# tc_board.net
KiCad netlist of a schematic drawn in EAGLE
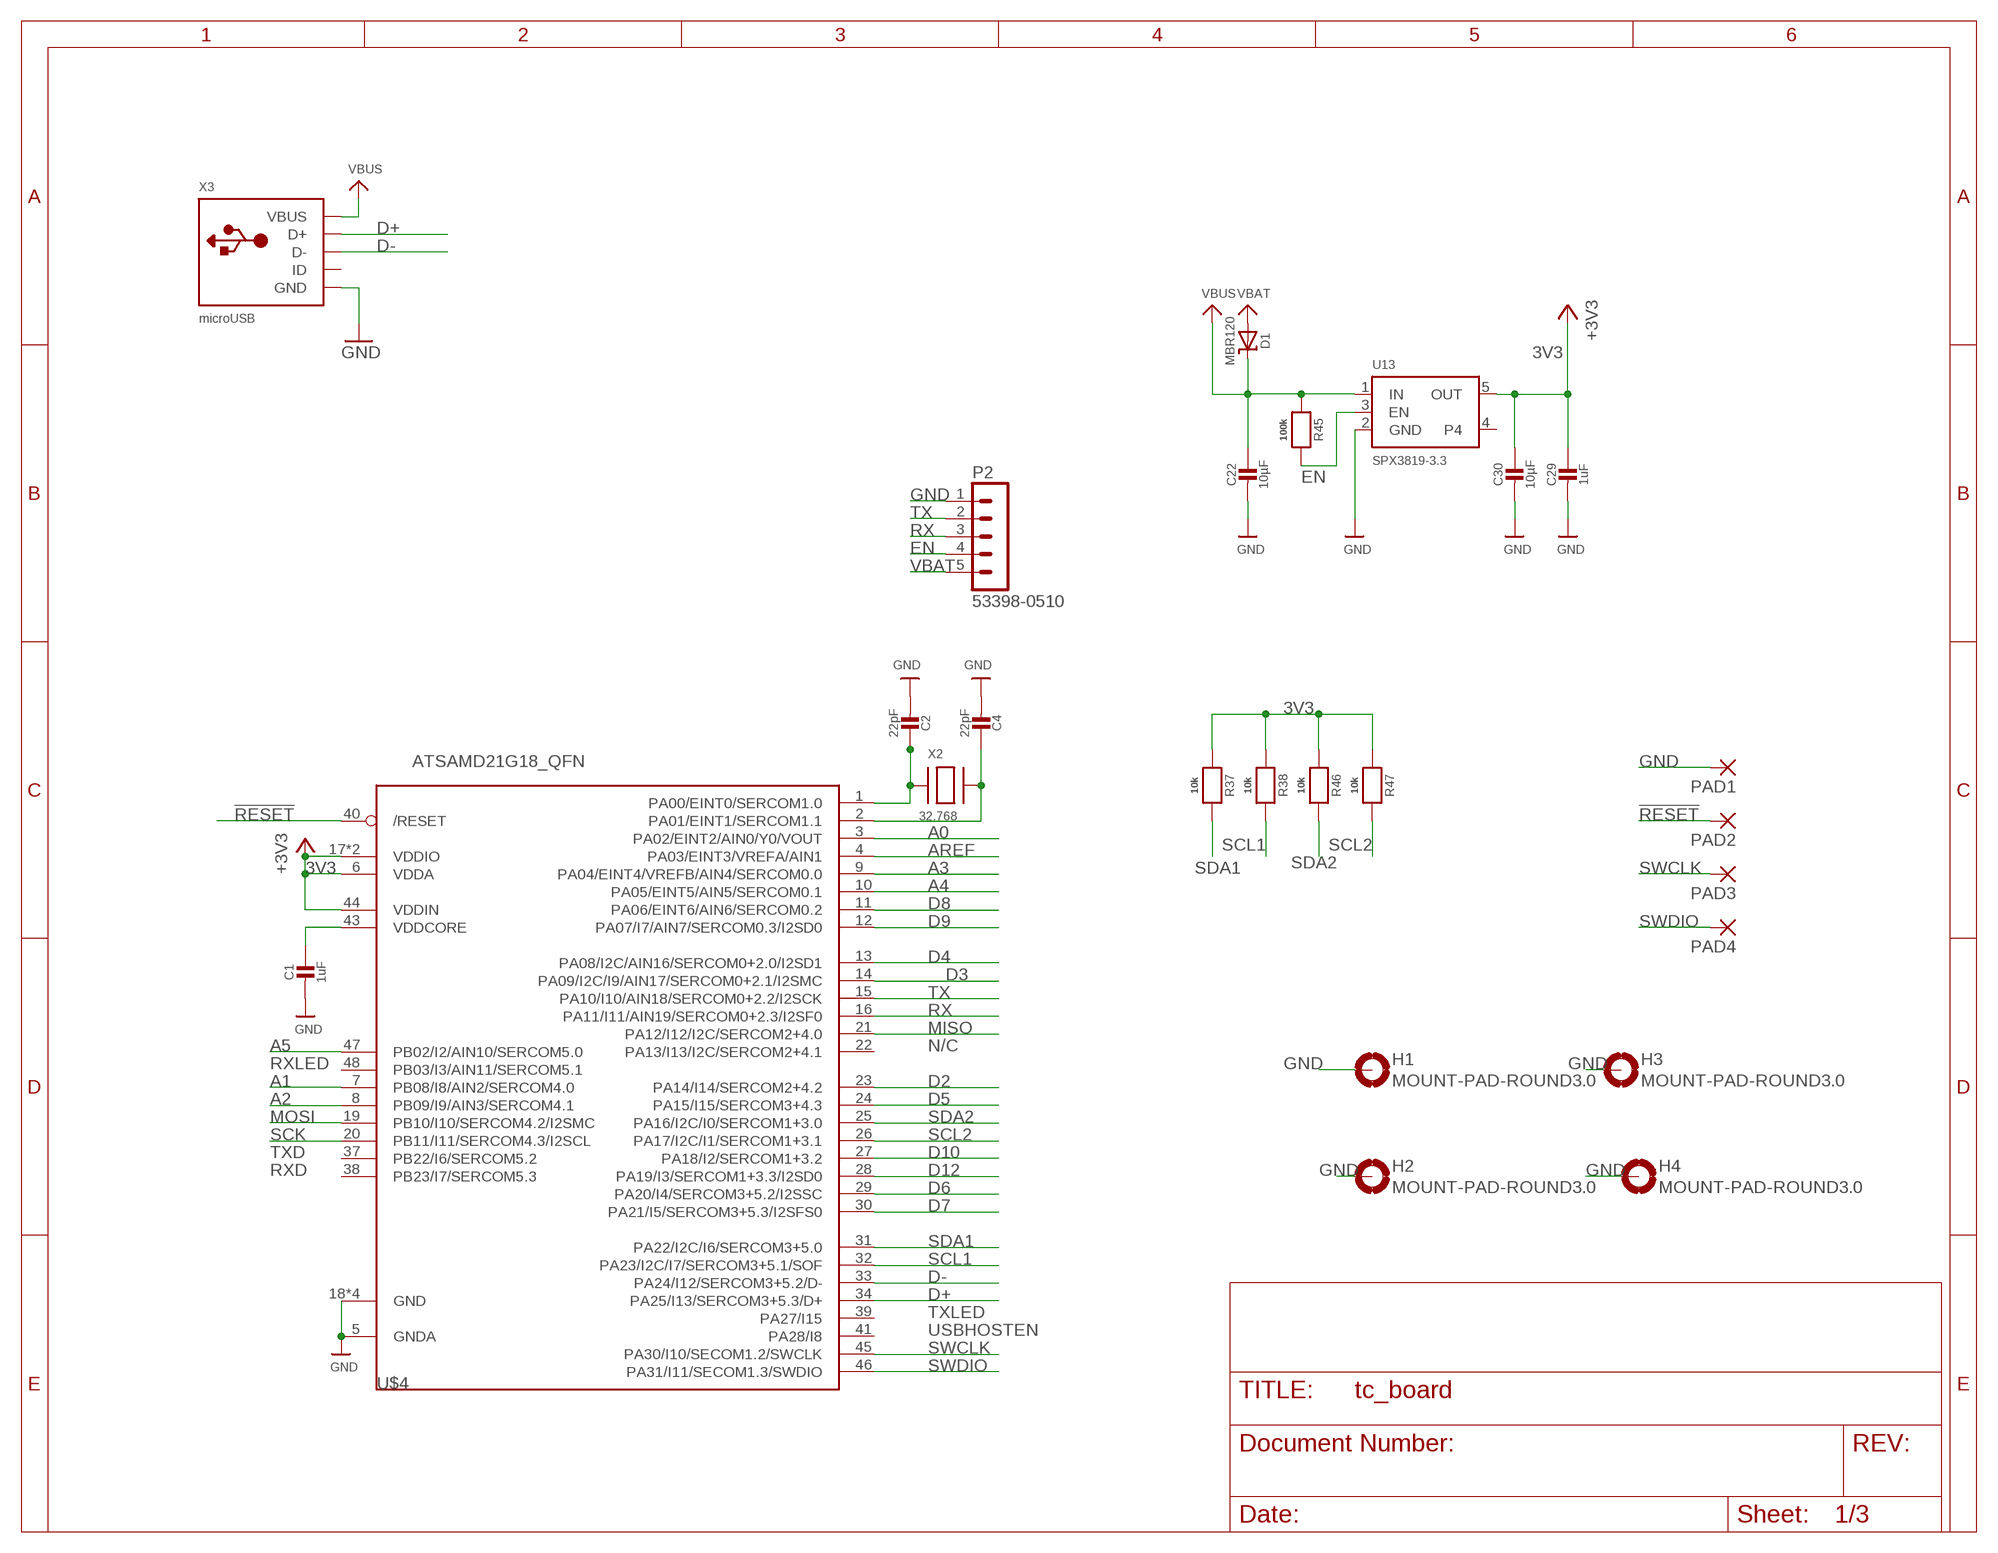
[diagram p0: schematic, sheet 1]
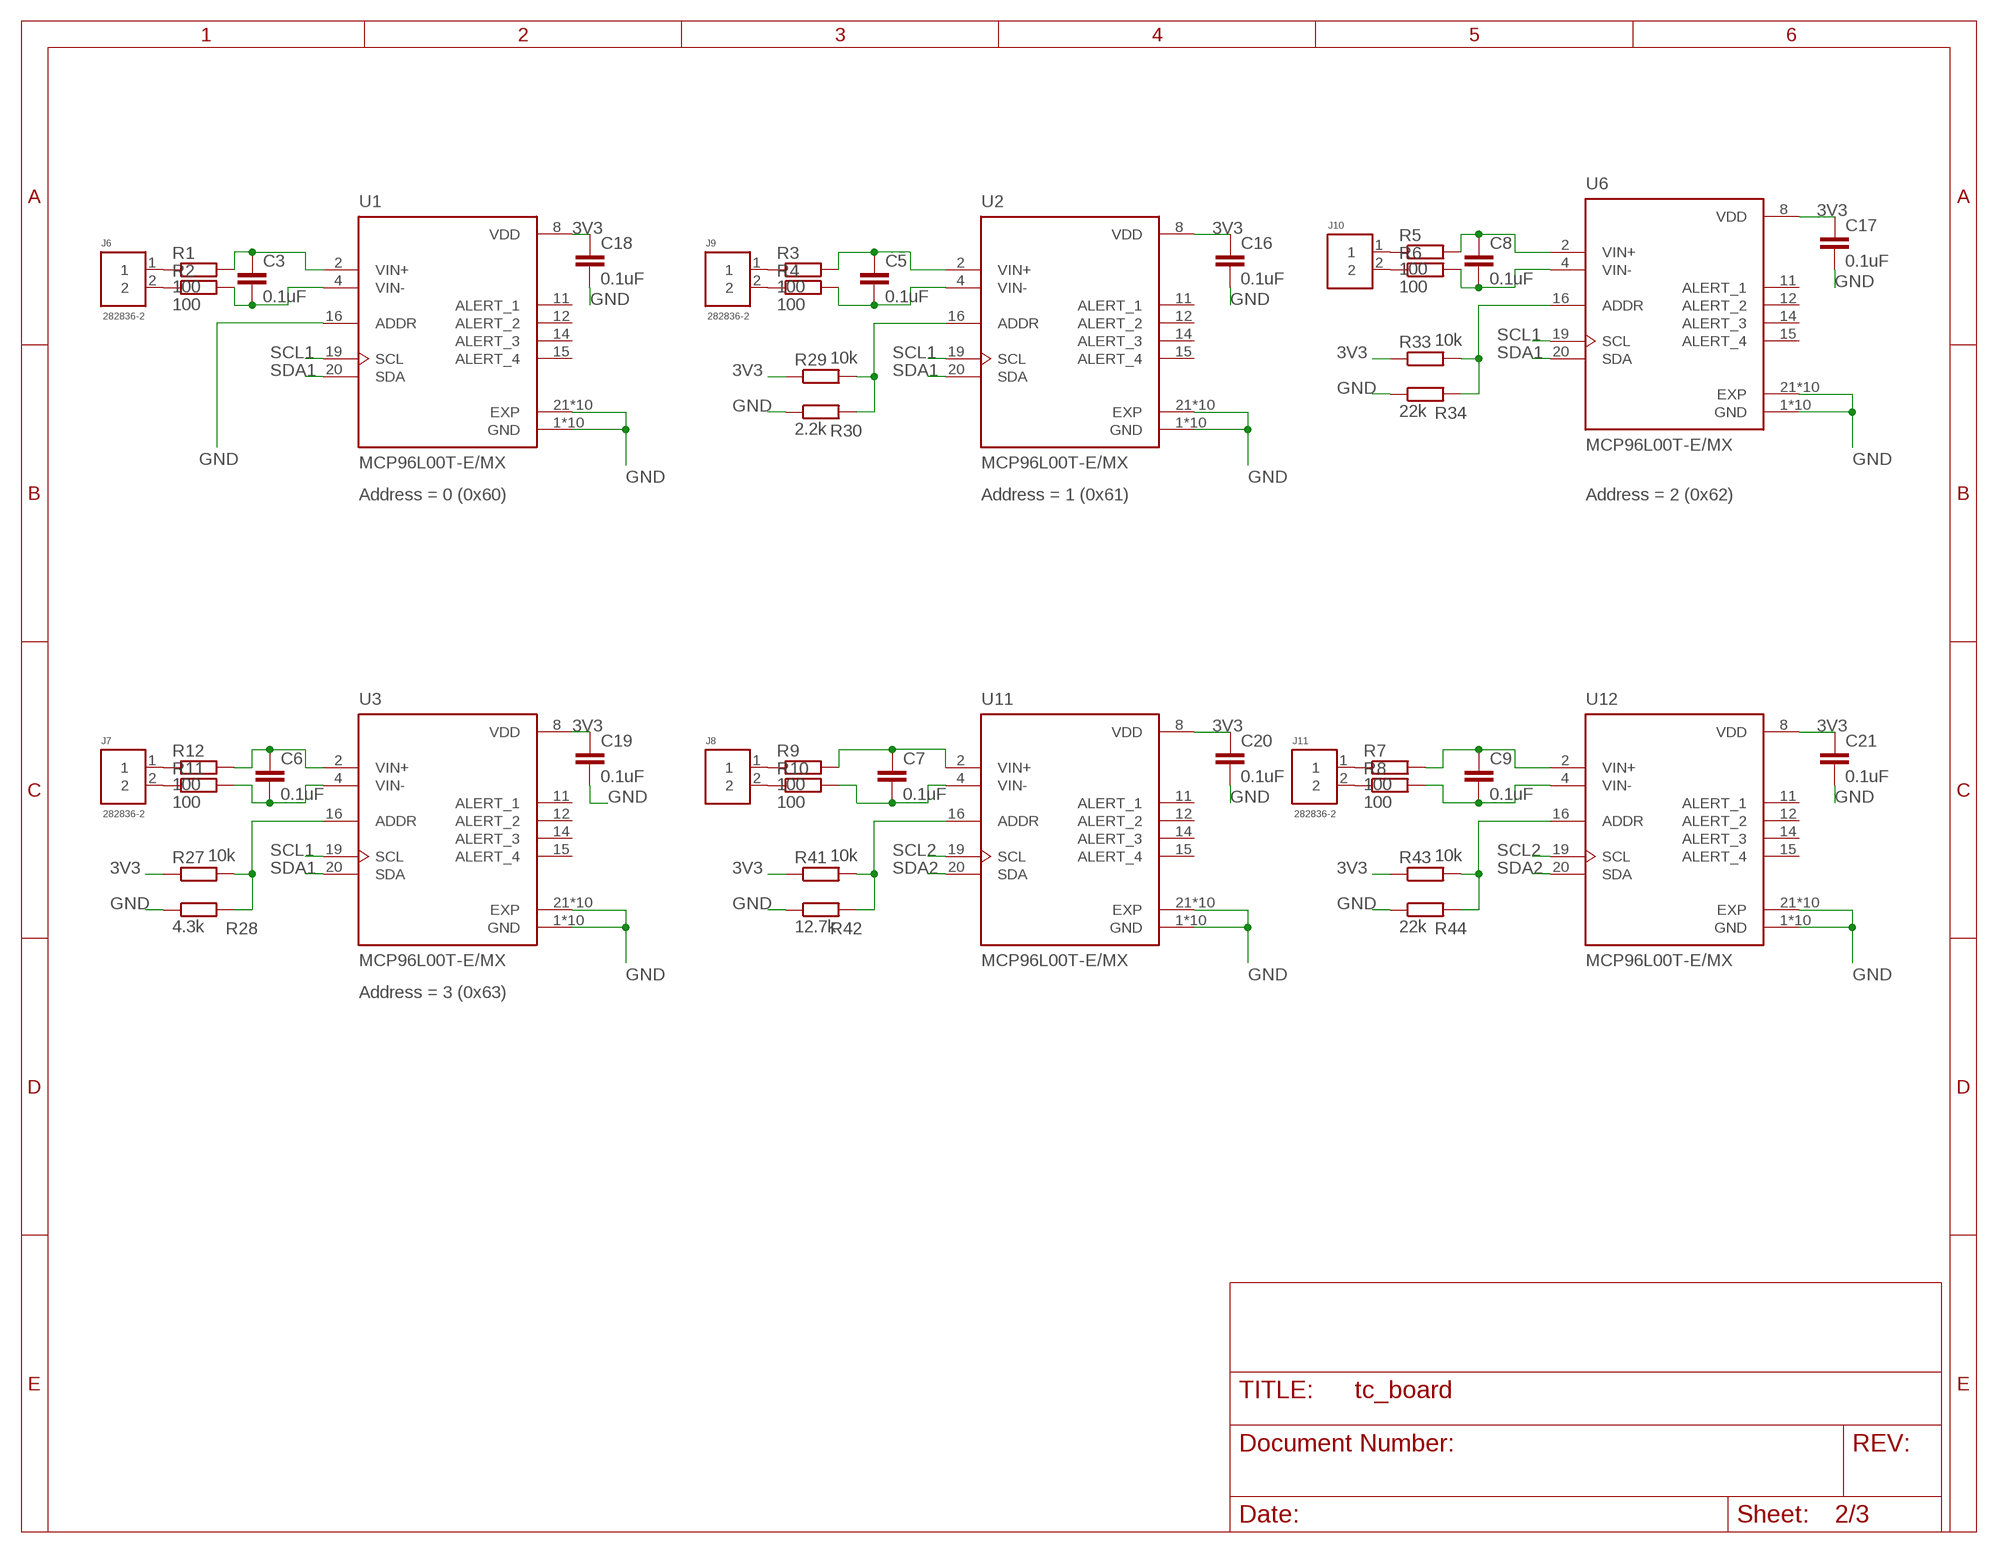
[diagram p1: schematic, sheet 2]
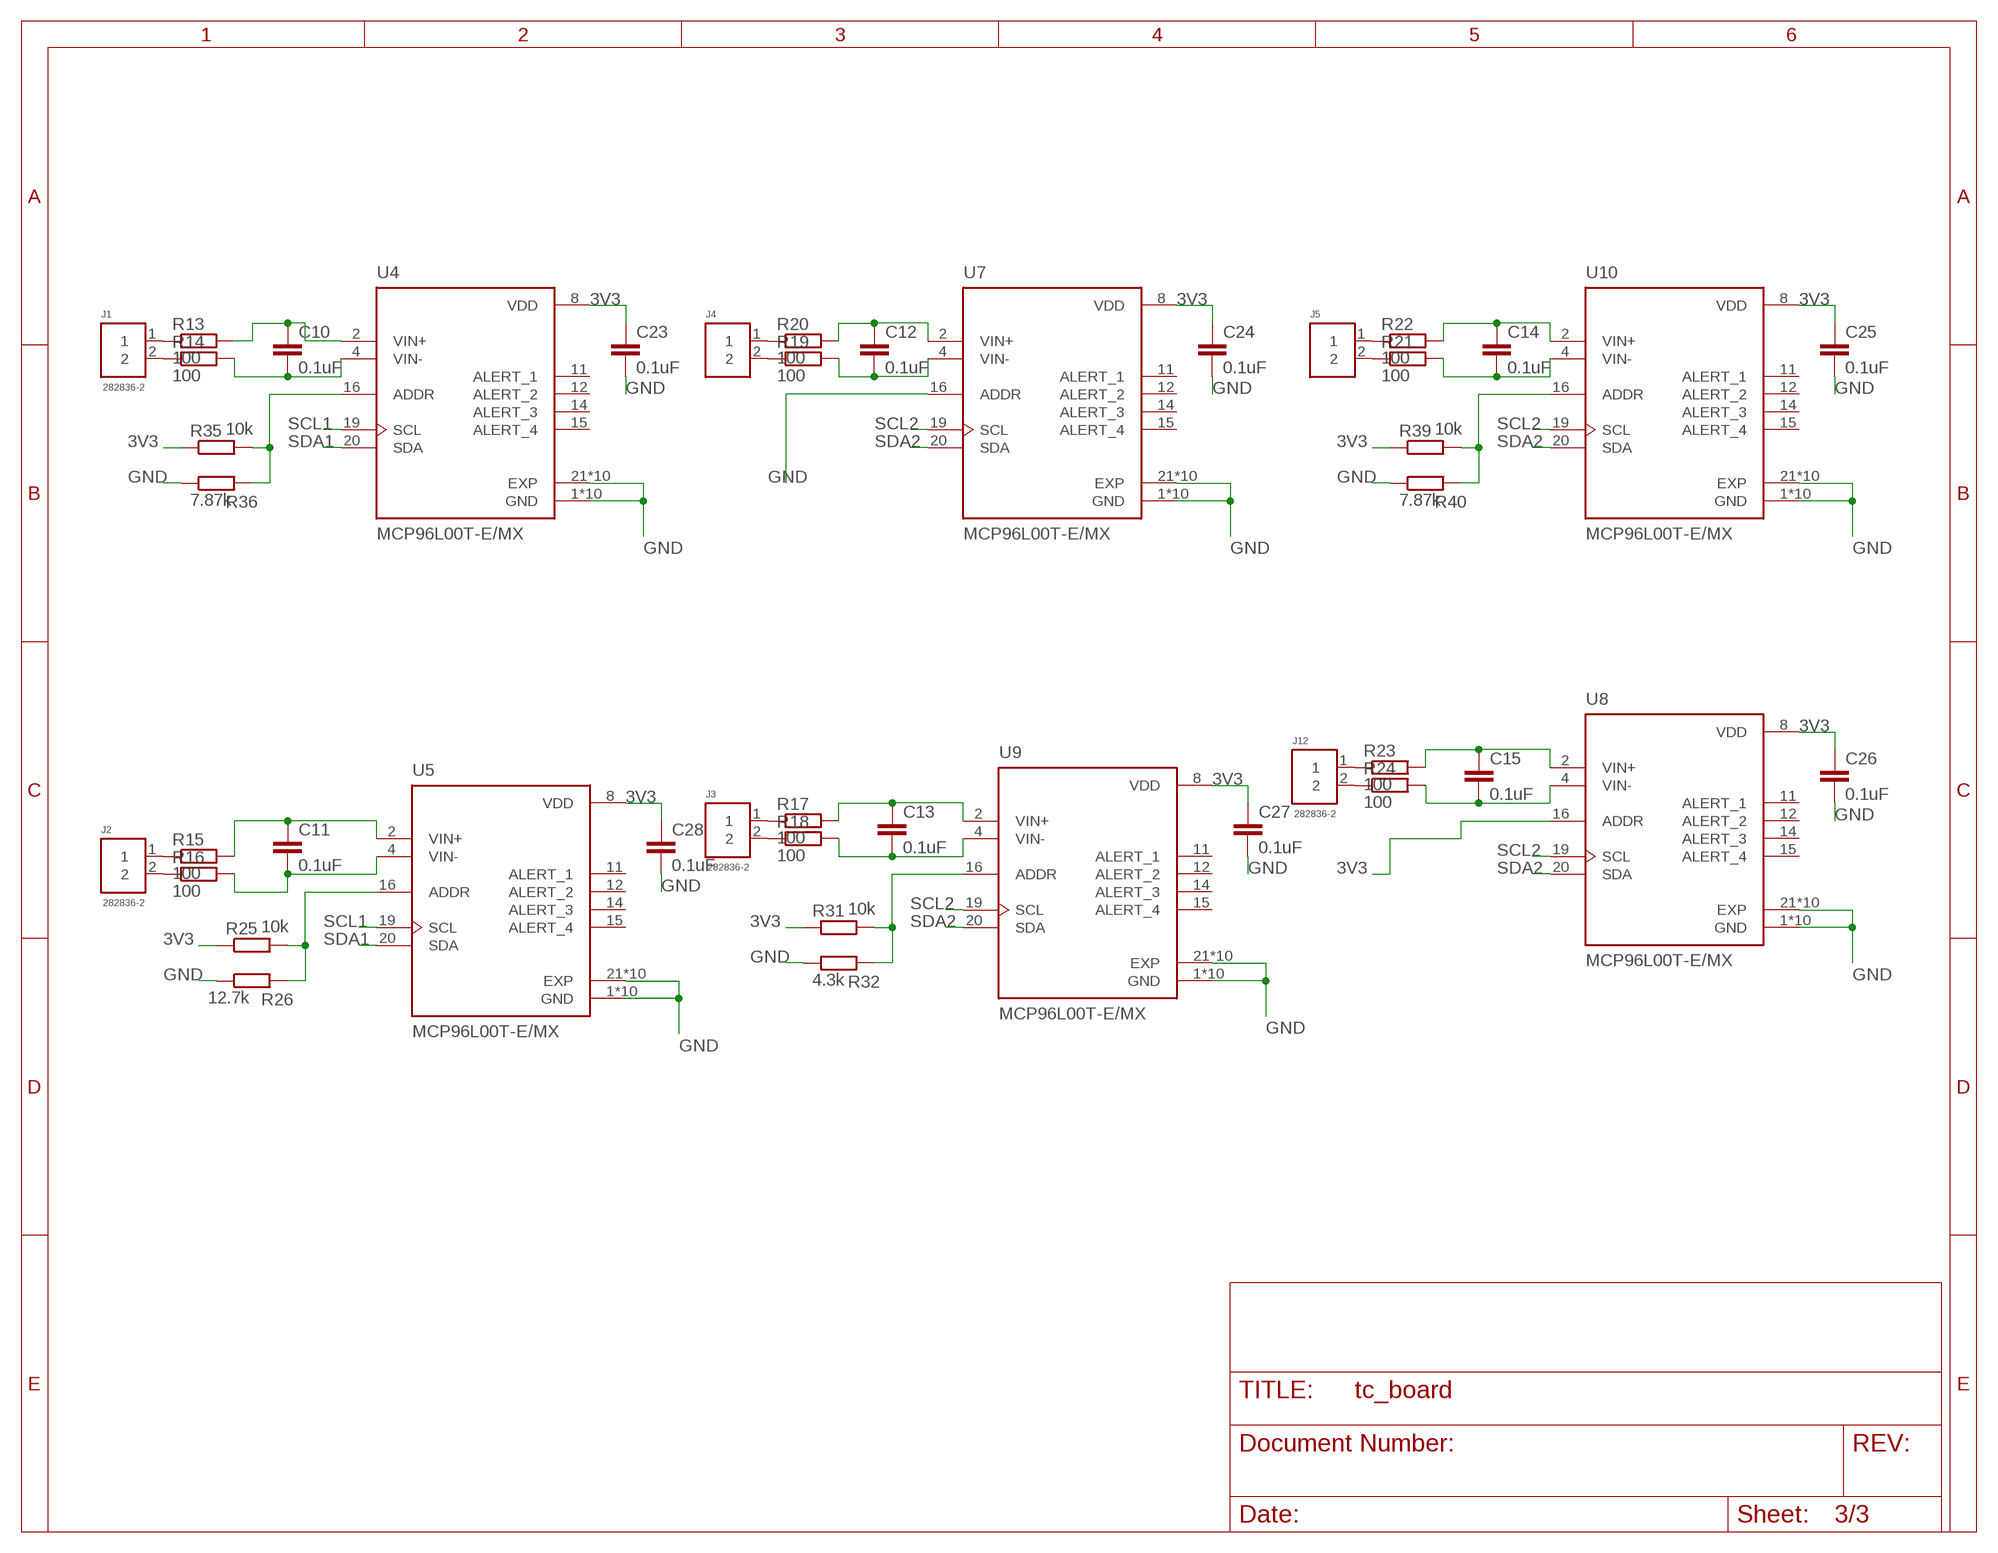
[diagram p2: schematic, sheet 3]

(export (version "E")
  (design (tool "Eeschema 10.0.6"))
  (components
    (comp (ref "C3")
      (value "0.1uF")
      (footprint "eagle-import:C0603")
      (libsource (lib "eagle-import") (part "C-EUC0603"))
    )
    (comp (ref "C5")
      (value "0.1uF")
      (footprint "eagle-import:C0603")
      (libsource (lib "eagle-import") (part "C-EUC0603"))
    )
    (comp (ref "C6")
      (value "0.1uF")
      (footprint "eagle-import:C0603")
      (libsource (lib "eagle-import") (part "C-EUC0603"))
    )
    (comp (ref "C7")
      (value "0.1uF")
      (footprint "eagle-import:C0603")
      (libsource (lib "eagle-import") (part "C-EUC0603"))
    )
    (comp (ref "C8")
      (value "0.1uF")
      (footprint "eagle-import:C0603")
      (libsource (lib "eagle-import") (part "C-EUC0603"))
    )
    (comp (ref "C9")
      (value "0.1uF")
      (footprint "eagle-import:C0603")
      (libsource (lib "eagle-import") (part "C-EUC0603"))
    )
    (comp (ref "C16")
      (value "0.1uF")
      (footprint "eagle-import:C0603")
      (libsource (lib "eagle-import") (part "C-EUC0603"))
    )
    (comp (ref "C17")
      (value "0.1uF")
      (footprint "eagle-import:C0603")
      (libsource (lib "eagle-import") (part "C-EUC0603"))
    )
    (comp (ref "C18")
      (value "0.1uF")
      (footprint "eagle-import:C0603")
      (libsource (lib "eagle-import") (part "C-EUC0603"))
    )
    (comp (ref "C19")
      (value "0.1uF")
      (footprint "eagle-import:C0603")
      (libsource (lib "eagle-import") (part "C-EUC0603"))
    )
    (comp (ref "C20")
      (value "0.1uF")
      (footprint "eagle-import:C0603")
      (libsource (lib "eagle-import") (part "C-EUC0603"))
    )
    (comp (ref "C21")
      (value "0.1uF")
      (footprint "eagle-import:C0603")
      (libsource (lib "eagle-import") (part "C-EUC0603"))
    )
    (comp (ref "J6")
      (value "282836-2")
      (footprint "eagle-import:CONN_282836-2")
      (fields (field (name "MF") "TE Connectivity") (field (name "MP") "2828362"))
      (libsource (lib "eagle-import") (part "282836-2"))
    )
    (comp (ref "J7")
      (value "282836-2")
      (footprint "eagle-import:CONN_282836-2")
      (fields (field (name "MF") "TE Connectivity") (field (name "MP") "2828362"))
      (libsource (lib "eagle-import") (part "282836-2"))
    )
    (comp (ref "J8")
      (value "282836-2")
      (footprint "eagle-import:CONN_282836-2")
      (fields (field (name "MF") "TE Connectivity") (field (name "MP") "2828362"))
      (libsource (lib "eagle-import") (part "282836-2"))
    )
    (comp (ref "J9")
      (value "282836-2")
      (footprint "eagle-import:CONN_282836-2")
      (fields (field (name "MF") "TE Connectivity") (field (name "MP") "2828362"))
      (libsource (lib "eagle-import") (part "282836-2"))
    )
    (comp (ref "J10")
      (value "282836-2")
      (footprint "eagle-import:CONN_282836-2")
      (fields (field (name "MF") "TE Connectivity") (field (name "MP") "2828362"))
      (libsource (lib "eagle-import") (part "282836-2"))
    )
    (comp (ref "J11")
      (value "282836-2")
      (footprint "eagle-import:CONN_282836-2")
      (fields (field (name "MF") "TE Connectivity") (field (name "MP") "2828362"))
      (libsource (lib "eagle-import") (part "282836-2"))
    )
    (comp (ref "R1")
      (value "100")
      (footprint "eagle-import:R0603")
      (libsource (lib "eagle-import") (part "R-EU_R0603"))
    )
    (comp (ref "R2")
      (value "100")
      (footprint "eagle-import:R0603")
      (libsource (lib "eagle-import") (part "R-EU_R0603"))
    )
    (comp (ref "R3")
      (value "100")
      (footprint "eagle-import:R0603")
      (libsource (lib "eagle-import") (part "R-EU_R0603"))
    )
    (comp (ref "R4")
      (value "100")
      (footprint "eagle-import:R0603")
      (libsource (lib "eagle-import") (part "R-EU_R0603"))
    )
    (comp (ref "R5")
      (value "100")
      (footprint "eagle-import:R0603")
      (libsource (lib "eagle-import") (part "R-EU_R0603"))
    )
    (comp (ref "R6")
      (value "100")
      (footprint "eagle-import:R0603")
      (libsource (lib "eagle-import") (part "R-EU_R0603"))
    )
    (comp (ref "R7")
      (value "100")
      (footprint "eagle-import:R0603")
      (libsource (lib "eagle-import") (part "R-EU_R0603"))
    )
    (comp (ref "R8")
      (value "100")
      (footprint "eagle-import:R0603")
      (libsource (lib "eagle-import") (part "R-EU_R0603"))
    )
    (comp (ref "R9")
      (value "100")
      (footprint "eagle-import:R0603")
      (libsource (lib "eagle-import") (part "R-EU_R0603"))
    )
    (comp (ref "R10")
      (value "100")
      (footprint "eagle-import:R0603")
      (libsource (lib "eagle-import") (part "R-EU_R0603"))
    )
    (comp (ref "R11")
      (value "100")
      (footprint "eagle-import:R0603")
      (libsource (lib "eagle-import") (part "R-EU_R0603"))
    )
    (comp (ref "R12")
      (value "100")
      (footprint "eagle-import:R0603")
      (libsource (lib "eagle-import") (part "R-EU_R0603"))
    )
    (comp (ref "R27")
      (value "10k")
      (footprint "eagle-import:R0603")
      (libsource (lib "eagle-import") (part "R-EU_R0603"))
    )
    (comp (ref "R28")
      (value "4.3k")
      (footprint "eagle-import:R0603")
      (libsource (lib "eagle-import") (part "R-EU_R0603"))
    )
    (comp (ref "R29")
      (value "10k")
      (footprint "eagle-import:R0603")
      (libsource (lib "eagle-import") (part "R-EU_R0603"))
    )
    (comp (ref "R30")
      (value "2.2k")
      (footprint "eagle-import:R0603")
      (libsource (lib "eagle-import") (part "R-EU_R0603"))
    )
    (comp (ref "R33")
      (value "10k")
      (footprint "eagle-import:R0603")
      (libsource (lib "eagle-import") (part "R-EU_R0603"))
    )
    (comp (ref "R34")
      (value "22k")
      (footprint "eagle-import:R0603")
      (libsource (lib "eagle-import") (part "R-EU_R0603"))
    )
    (comp (ref "R41")
      (value "10k")
      (footprint "eagle-import:R0603")
      (libsource (lib "eagle-import") (part "R-EU_R0603"))
    )
    (comp (ref "R42")
      (value "12.7k")
      (footprint "eagle-import:R0603")
      (libsource (lib "eagle-import") (part "R-EU_R0603"))
    )
    (comp (ref "R43")
      (value "10k")
      (footprint "eagle-import:R0603")
      (libsource (lib "eagle-import") (part "R-EU_R0603"))
    )
    (comp (ref "R44")
      (value "22k")
      (footprint "eagle-import:R0603")
      (libsource (lib "eagle-import") (part "R-EU_R0603"))
    )
    (comp (ref "U1")
      (value "MCP96L00T-E/MX")
      (footprint "eagle-import:QFN65P500X500X100-21N_MCP96L00T-E_MX")
      (fields
        (field (name "DIGI-KEY_PART_NUMBER") "MCP96L00T-E/MXCT-ND")
        (field (name "MF") "Microchip Technology")
      )
      (libsource (lib "eagle-import") (part "MCP96L00T-E/MX"))
    )
    (comp (ref "U2")
      (value "MCP96L00T-E/MX")
      (footprint "eagle-import:QFN65P500X500X100-21N_MCP96L00T-E_MX")
      (fields
        (field (name "DIGI-KEY_PART_NUMBER") "MCP96L00T-E/MXCT-ND")
        (field (name "MF") "Microchip Technology")
      )
      (libsource (lib "eagle-import") (part "MCP96L00T-E/MX"))
    )
    (comp (ref "U3")
      (value "MCP96L00T-E/MX")
      (footprint "eagle-import:QFN65P500X500X100-21N_MCP96L00T-E_MX")
      (fields
        (field (name "DIGI-KEY_PART_NUMBER") "MCP96L00T-E/MXCT-ND")
        (field (name "MF") "Microchip Technology")
      )
      (libsource (lib "eagle-import") (part "MCP96L00T-E/MX"))
    )
    (comp (ref "U6")
      (value "MCP96L00T-E/MX")
      (footprint "eagle-import:QFN65P500X500X100-21N_MCP96L00T-E_MX")
      (fields
        (field (name "DIGI-KEY_PART_NUMBER") "MCP96L00T-E/MXCT-ND")
        (field (name "MF") "Microchip Technology")
      )
      (libsource (lib "eagle-import") (part "MCP96L00T-E/MX"))
    )
    (comp (ref "U11")
      (value "MCP96L00T-E/MX")
      (footprint "eagle-import:QFN65P500X500X100-21N_MCP96L00T-E_MX")
      (fields
        (field (name "DIGI-KEY_PART_NUMBER") "MCP96L00T-E/MXCT-ND")
        (field (name "MF") "Microchip Technology")
      )
      (libsource (lib "eagle-import") (part "MCP96L00T-E/MX"))
    )
    (comp (ref "U12")
      (value "MCP96L00T-E/MX")
      (footprint "eagle-import:QFN65P500X500X100-21N_MCP96L00T-E_MX")
      (fields
        (field (name "DIGI-KEY_PART_NUMBER") "MCP96L00T-E/MXCT-ND")
        (field (name "MF") "Microchip Technology")
      )
      (libsource (lib "eagle-import") (part "MCP96L00T-E/MX"))
    )
    (comp (ref "C1")
      (value "1uF")
      (footprint "eagle-import:0603-NO")
      (libsource (lib "eagle-import") (part "CAP_CERAMIC0603_NO"))
    )
    (comp (ref "C2")
      (value "22pF")
      (footprint "eagle-import:0603-NO")
      (libsource (lib "eagle-import") (part "CAP_CERAMIC0603_NO"))
    )
    (comp (ref "C4")
      (value "22pF")
      (footprint "eagle-import:0603-NO")
      (libsource (lib "eagle-import") (part "CAP_CERAMIC0603_NO"))
    )
    (comp (ref "C22")
      (value "10µF")
      (footprint "eagle-import:0805-NO")
      (libsource (lib "eagle-import") (part "CAP_CERAMIC0805-NOOUTLINE"))
    )
    (comp (ref "C29")
      (value "1uF")
      (footprint "eagle-import:0603-NO")
      (libsource (lib "eagle-import") (part "CAP_CERAMIC0603_NO"))
    )
    (comp (ref "C30")
      (value "10µF")
      (footprint "eagle-import:0805-NO")
      (libsource (lib "eagle-import") (part "CAP_CERAMIC0805-NOOUTLINE"))
    )
    (comp (ref "D1")
      (value "MBR120")
      (footprint "eagle-import:SOD-123")
      (libsource (lib "eagle-import") (part "DIODE-SCHOTTKYSOD-123"))
    )
    (comp (ref "H1")
      (value "MOUNT-PAD-ROUND3.0")
      (footprint "eagle-import:3,0-PAD")
      (libsource (lib "eagle-import") (part "MOUNT-PAD-ROUND3.0"))
    )
    (comp (ref "H2")
      (value "MOUNT-PAD-ROUND3.0")
      (footprint "eagle-import:3,0-PAD")
      (libsource (lib "eagle-import") (part "MOUNT-PAD-ROUND3.0"))
    )
    (comp (ref "H3")
      (value "MOUNT-PAD-ROUND3.0")
      (footprint "eagle-import:3,0-PAD")
      (libsource (lib "eagle-import") (part "MOUNT-PAD-ROUND3.0"))
    )
    (comp (ref "H4")
      (value "MOUNT-PAD-ROUND3.0")
      (footprint "eagle-import:3,0-PAD")
      (libsource (lib "eagle-import") (part "MOUNT-PAD-ROUND3.0"))
    )
    (comp (ref "P2")
      (value "53398-0510")
      (footprint "eagle-import:53398-0510")
      (libsource (lib "eagle-import") (part "53398-0510"))
    )
    (comp (ref "PAD1")
      (value "SMD2")
      (footprint "eagle-import:SMD1,27-2,54")
      (libsource (lib "eagle-import") (part "SMD2"))
    )
    (comp (ref "PAD2")
      (value "SMD2")
      (footprint "eagle-import:SMD1,27-2,54")
      (libsource (lib "eagle-import") (part "SMD2"))
    )
    (comp (ref "PAD3")
      (value "SMD2")
      (footprint "eagle-import:SMD1,27-2,54")
      (libsource (lib "eagle-import") (part "SMD2"))
    )
    (comp (ref "PAD4")
      (value "SMD2")
      (footprint "eagle-import:SMD1,27-2,54")
      (libsource (lib "eagle-import") (part "SMD2"))
    )
    (comp (ref "R37")
      (value "10k")
      (footprint "eagle-import:0603-NO")
      (libsource (lib "eagle-import") (part "RESISTOR_0603_NOOUT"))
    )
    (comp (ref "R38")
      (value "10k")
      (footprint "eagle-import:0603-NO")
      (libsource (lib "eagle-import") (part "RESISTOR_0603_NOOUT"))
    )
    (comp (ref "R45")
      (value "100k")
      (footprint "eagle-import:0603-NO")
      (libsource (lib "eagle-import") (part "RESISTOR_0603_NOOUT"))
    )
    (comp (ref "R46")
      (value "10k")
      (footprint "eagle-import:0603-NO")
      (libsource (lib "eagle-import") (part "RESISTOR_0603_NOOUT"))
    )
    (comp (ref "R47")
      (value "10k")
      (footprint "eagle-import:0603-NO")
      (libsource (lib "eagle-import") (part "RESISTOR_0603_NOOUT"))
    )
    (comp (ref "U$4")
      (value "ATSAMD21G18_QFN")
      (footprint "eagle-import:TQFN48_7MM")
      (libsource (lib "eagle-import") (part "ATSAMD21J_QFN"))
    )
    (comp (ref "U13")
      (value "SPX3819-3.3")
      (footprint "eagle-import:SOT23-5")
      (libsource (lib "eagle-import") (part "VREG_SOT23-5"))
    )
    (comp (ref "X2")
      (value "32.768")
      (footprint "eagle-import:XTAL3215")
      (libsource (lib "eagle-import") (part "XTAL-3.2X1.5"))
    )
    (comp (ref "X3")
      (value "microUSB")
      (footprint "eagle-import:4UCONN_20329_V2")
      (libsource (lib "eagle-import") (part "USB_MICRO_20329_V2"))
    )
    (comp (ref "C10")
      (value "0.1uF")
      (footprint "eagle-import:C0603")
      (libsource (lib "eagle-import") (part "C-EUC0603"))
    )
    (comp (ref "C11")
      (value "0.1uF")
      (footprint "eagle-import:C0603")
      (libsource (lib "eagle-import") (part "C-EUC0603"))
    )
    (comp (ref "C12")
      (value "0.1uF")
      (footprint "eagle-import:C0603")
      (libsource (lib "eagle-import") (part "C-EUC0603"))
    )
    (comp (ref "C13")
      (value "0.1uF")
      (footprint "eagle-import:C0603")
      (libsource (lib "eagle-import") (part "C-EUC0603"))
    )
    (comp (ref "C14")
      (value "0.1uF")
      (footprint "eagle-import:C0603")
      (libsource (lib "eagle-import") (part "C-EUC0603"))
    )
    (comp (ref "C15")
      (value "0.1uF")
      (footprint "eagle-import:C0603")
      (libsource (lib "eagle-import") (part "C-EUC0603"))
    )
    (comp (ref "C23")
      (value "0.1uF")
      (footprint "eagle-import:C0603")
      (libsource (lib "eagle-import") (part "C-EUC0603"))
    )
    (comp (ref "C24")
      (value "0.1uF")
      (footprint "eagle-import:C0603")
      (libsource (lib "eagle-import") (part "C-EUC0603"))
    )
    (comp (ref "C25")
      (value "0.1uF")
      (footprint "eagle-import:C0603")
      (libsource (lib "eagle-import") (part "C-EUC0603"))
    )
    (comp (ref "C26")
      (value "0.1uF")
      (footprint "eagle-import:C0603")
      (libsource (lib "eagle-import") (part "C-EUC0603"))
    )
    (comp (ref "C27")
      (value "0.1uF")
      (footprint "eagle-import:C0603")
      (libsource (lib "eagle-import") (part "C-EUC0603"))
    )
    (comp (ref "C28")
      (value "0.1uF")
      (footprint "eagle-import:C0603")
      (libsource (lib "eagle-import") (part "C-EUC0603"))
    )
    (comp (ref "J1")
      (value "282836-2")
      (footprint "eagle-import:CONN_282836-2")
      (fields (field (name "MF") "TE Connectivity") (field (name "MP") "2828362"))
      (libsource (lib "eagle-import") (part "282836-2"))
    )
    (comp (ref "J2")
      (value "282836-2")
      (footprint "eagle-import:CONN_282836-2")
      (fields (field (name "MF") "TE Connectivity") (field (name "MP") "2828362"))
      (libsource (lib "eagle-import") (part "282836-2"))
    )
    (comp (ref "J3")
      (value "282836-2")
      (footprint "eagle-import:CONN_282836-2")
      (fields (field (name "MF") "TE Connectivity") (field (name "MP") "2828362"))
      (libsource (lib "eagle-import") (part "282836-2"))
    )
    (comp (ref "J4")
      (value "282836-2")
      (footprint "eagle-import:CONN_282836-2")
      (fields (field (name "MF") "TE Connectivity") (field (name "MP") "2828362"))
      (libsource (lib "eagle-import") (part "282836-2"))
    )
    (comp (ref "J5")
      (value "282836-2")
      (footprint "eagle-import:CONN_282836-2")
      (fields (field (name "MF") "TE Connectivity") (field (name "MP") "2828362"))
      (libsource (lib "eagle-import") (part "282836-2"))
    )
    (comp (ref "J12")
      (value "282836-2")
      (footprint "eagle-import:CONN_282836-2")
      (fields (field (name "MF") "TE Connectivity") (field (name "MP") "2828362"))
      (libsource (lib "eagle-import") (part "282836-2"))
    )
    (comp (ref "R13")
      (value "100")
      (footprint "eagle-import:R0603")
      (libsource (lib "eagle-import") (part "R-EU_R0603"))
    )
    (comp (ref "R14")
      (value "100")
      (footprint "eagle-import:R0603")
      (libsource (lib "eagle-import") (part "R-EU_R0603"))
    )
    (comp (ref "R15")
      (value "100")
      (footprint "eagle-import:R0603")
      (libsource (lib "eagle-import") (part "R-EU_R0603"))
    )
    (comp (ref "R16")
      (value "100")
      (footprint "eagle-import:R0603")
      (libsource (lib "eagle-import") (part "R-EU_R0603"))
    )
    (comp (ref "R17")
      (value "100")
      (footprint "eagle-import:R0603")
      (libsource (lib "eagle-import") (part "R-EU_R0603"))
    )
    (comp (ref "R18")
      (value "100")
      (footprint "eagle-import:R0603")
      (libsource (lib "eagle-import") (part "R-EU_R0603"))
    )
    (comp (ref "R19")
      (value "100")
      (footprint "eagle-import:R0603")
      (libsource (lib "eagle-import") (part "R-EU_R0603"))
    )
    (comp (ref "R20")
      (value "100")
      (footprint "eagle-import:R0603")
      (libsource (lib "eagle-import") (part "R-EU_R0603"))
    )
    (comp (ref "R21")
      (value "100")
      (footprint "eagle-import:R0603")
      (libsource (lib "eagle-import") (part "R-EU_R0603"))
    )
    (comp (ref "R22")
      (value "100")
      (footprint "eagle-import:R0603")
      (libsource (lib "eagle-import") (part "R-EU_R0603"))
    )
    (comp (ref "R23")
      (value "100")
      (footprint "eagle-import:R0603")
      (libsource (lib "eagle-import") (part "R-EU_R0603"))
    )
    (comp (ref "R24")
      (value "100")
      (footprint "eagle-import:R0603")
      (libsource (lib "eagle-import") (part "R-EU_R0603"))
    )
    (comp (ref "R25")
      (value "10k")
      (footprint "eagle-import:R0603")
      (libsource (lib "eagle-import") (part "R-EU_R0603"))
    )
    (comp (ref "R26")
      (value "12.7k")
      (footprint "eagle-import:R0603")
      (libsource (lib "eagle-import") (part "R-EU_R0603"))
    )
    (comp (ref "R31")
      (value "10k")
      (footprint "eagle-import:R0603")
      (libsource (lib "eagle-import") (part "R-EU_R0603"))
    )
    (comp (ref "R32")
      (value "4.3k")
      (footprint "eagle-import:R0603")
      (libsource (lib "eagle-import") (part "R-EU_R0603"))
    )
    (comp (ref "R35")
      (value "10k")
      (footprint "eagle-import:R0603")
      (libsource (lib "eagle-import") (part "R-EU_R0603"))
    )
    (comp (ref "R36")
      (value "7.87k")
      (footprint "eagle-import:R0603")
      (libsource (lib "eagle-import") (part "R-EU_R0603"))
    )
    (comp (ref "R39")
      (value "10k")
      (footprint "eagle-import:R0603")
      (libsource (lib "eagle-import") (part "R-EU_R0603"))
    )
    (comp (ref "R40")
      (value "7.87k")
      (footprint "eagle-import:R0603")
      (libsource (lib "eagle-import") (part "R-EU_R0603"))
    )
    (comp (ref "U4")
      (value "MCP96L00T-E/MX")
      (footprint "eagle-import:QFN65P500X500X100-21N_MCP96L00T-E_MX")
      (fields
        (field (name "DIGI-KEY_PART_NUMBER") "MCP96L00T-E/MXCT-ND")
        (field (name "MF") "Microchip Technology")
      )
      (libsource (lib "eagle-import") (part "MCP96L00T-E/MX"))
    )
    (comp (ref "U5")
      (value "MCP96L00T-E/MX")
      (footprint "eagle-import:QFN65P500X500X100-21N_MCP96L00T-E_MX")
      (fields
        (field (name "DIGI-KEY_PART_NUMBER") "MCP96L00T-E/MXCT-ND")
        (field (name "MF") "Microchip Technology")
      )
      (libsource (lib "eagle-import") (part "MCP96L00T-E/MX"))
    )
    (comp (ref "U7")
      (value "MCP96L00T-E/MX")
      (footprint "eagle-import:QFN65P500X500X100-21N_MCP96L00T-E_MX")
      (fields
        (field (name "DIGI-KEY_PART_NUMBER") "MCP96L00T-E/MXCT-ND")
        (field (name "MF") "Microchip Technology")
      )
      (libsource (lib "eagle-import") (part "MCP96L00T-E/MX"))
    )
    (comp (ref "U8")
      (value "MCP96L00T-E/MX")
      (footprint "eagle-import:QFN65P500X500X100-21N_MCP96L00T-E_MX")
      (fields
        (field (name "DIGI-KEY_PART_NUMBER") "MCP96L00T-E/MXCT-ND")
        (field (name "MF") "Microchip Technology")
      )
      (libsource (lib "eagle-import") (part "MCP96L00T-E/MX"))
    )
    (comp (ref "U9")
      (value "MCP96L00T-E/MX")
      (footprint "eagle-import:QFN65P500X500X100-21N_MCP96L00T-E_MX")
      (fields
        (field (name "DIGI-KEY_PART_NUMBER") "MCP96L00T-E/MXCT-ND")
        (field (name "MF") "Microchip Technology")
      )
      (libsource (lib "eagle-import") (part "MCP96L00T-E/MX"))
    )
    (comp (ref "U10")
      (value "MCP96L00T-E/MX")
      (footprint "eagle-import:QFN65P500X500X100-21N_MCP96L00T-E_MX")
      (fields
        (field (name "DIGI-KEY_PART_NUMBER") "MCP96L00T-E/MXCT-ND")
        (field (name "MF") "Microchip Technology")
      )
      (libsource (lib "eagle-import") (part "MCP96L00T-E/MX"))
    )
  )
  (nets
    (net (code "1") (name "3V3") (class "Default")
      (node (ref "C16") (pin "1") (pinfunction "1_1") (pintype "passive"))
      (node (ref "C17") (pin "1") (pinfunction "1_1") (pintype "passive"))
      (node (ref "C18") (pin "1") (pinfunction "1_1") (pintype "passive"))
      (node (ref "C19") (pin "1") (pinfunction "1_1") (pintype "passive"))
      (node (ref "C20") (pin "1") (pinfunction "1_1") (pintype "passive"))
      (node (ref "C21") (pin "1") (pinfunction "1_1") (pintype "passive"))
      (node (ref "C23") (pin "1") (pinfunction "1_1") (pintype "passive"))
      (node (ref "C24") (pin "1") (pinfunction "1_1") (pintype "passive"))
      (node (ref "C25") (pin "1") (pinfunction "1_1") (pintype "passive"))
      (node (ref "C26") (pin "1") (pinfunction "1_1") (pintype "passive"))
      (node (ref "C27") (pin "1") (pinfunction "1_1") (pintype "passive"))
      (node (ref "C28") (pin "1") (pinfunction "1_1") (pintype "passive"))
      (node (ref "C29") (pin "1") (pinfunction "1_1") (pintype "passive"))
      (node (ref "C30") (pin "1") (pinfunction "1_1") (pintype "passive"))
      (node (ref "R25") (pin "1") (pinfunction "1_1") (pintype "passive"))
      (node (ref "R27") (pin "1") (pinfunction "1_1") (pintype "passive"))
      (node (ref "R29") (pin "1") (pinfunction "1_1") (pintype "passive"))
      (node (ref "R31") (pin "1") (pinfunction "1_1") (pintype "passive"))
      (node (ref "R33") (pin "1") (pinfunction "1_1") (pintype "passive"))
      (node (ref "R35") (pin "1") (pinfunction "1_1") (pintype "passive"))
      (node (ref "R37") (pin "1") (pinfunction "1_1") (pintype "passive"))
      (node (ref "R38") (pin "1") (pinfunction "1_1") (pintype "passive"))
      (node (ref "R39") (pin "1") (pinfunction "1_1") (pintype "passive"))
      (node (ref "R41") (pin "1") (pinfunction "1_1") (pintype "passive"))
      (node (ref "R43") (pin "1") (pinfunction "1_1") (pintype "passive"))
      (node (ref "R46") (pin "1") (pinfunction "1_1") (pintype "passive"))
      (node (ref "R47") (pin "1") (pinfunction "1_1") (pintype "passive"))
      (node (ref "U$4") (pin "17") (pinfunction "VDDIO_17") (pintype "power_in"))
      (node (ref "U$4") (pin "36") (pinfunction "VDDIO_36") (pintype "power_in"))
      (node (ref "U$4") (pin "44") (pinfunction "VDDIN_44") (pintype "power_in"))
      (node (ref "U$4") (pin "6") (pinfunction "VDDA_6") (pintype "power_in"))
      (node (ref "U1") (pin "8") (pinfunction "VDD_8") (pintype "power_in"))
      (node (ref "U10") (pin "8") (pinfunction "VDD_8") (pintype "power_in"))
      (node (ref "U11") (pin "8") (pinfunction "VDD_8") (pintype "power_in"))
      (node (ref "U12") (pin "8") (pinfunction "VDD_8") (pintype "power_in"))
      (node (ref "U13") (pin "5") (pinfunction "OUT_5") (pintype "power_in"))
      (node (ref "U2") (pin "8") (pinfunction "VDD_8") (pintype "power_in"))
      (node (ref "U3") (pin "8") (pinfunction "VDD_8") (pintype "power_in"))
      (node (ref "U4") (pin "8") (pinfunction "VDD_8") (pintype "power_in"))
      (node (ref "U5") (pin "8") (pinfunction "VDD_8") (pintype "power_in"))
      (node (ref "U6") (pin "8") (pinfunction "VDD_8") (pintype "power_in"))
      (node (ref "U7") (pin "8") (pinfunction "VDD_8") (pintype "power_in"))
      (node (ref "U8") (pin "16") (pinfunction "ADDR_16") (pintype "input"))
      (node (ref "U8") (pin "8") (pinfunction "VDD_8") (pintype "power_in"))
      (node (ref "U9") (pin "8") (pinfunction "VDD_8") (pintype "power_in"))
    )
    (net (code "2") (name "A0") (class "Default")
      (node (ref "U$4") (pin "3") (pinfunction "PA02/EINT2/AIN0/Y0/VOUT_3") (pintype "bidirectional"))
    )
    (net (code "3") (name "A1") (class "Default")
      (node (ref "U$4") (pin "7") (pinfunction "PB08/I8/AIN2/SERCOM4.0_7") (pintype "bidirectional"))
    )
    (net (code "4") (name "A2") (class "Default")
      (node (ref "U$4") (pin "8") (pinfunction "PB09/I9/AIN3/SERCOM4.1_8") (pintype "bidirectional"))
    )
    (net (code "5") (name "A3") (class "Default")
      (node (ref "U$4") (pin "9") (pinfunction "PA04/EINT4/VREFB/AIN4/SERCOM0.0_9") (pintype "bidirectional"))
    )
    (net (code "6") (name "A4") (class "Default")
      (node (ref "U$4") (pin "10") (pinfunction "PA05/EINT5/AIN5/SERCOM0.1_10") (pintype "bidirectional"))
    )
    (net (code "7") (name "A5") (class "Default")
      (node (ref "U$4") (pin "47") (pinfunction "PB02/I2/AIN10/SERCOM5.0_47") (pintype "bidirectional"))
    )
    (net (code "8") (name "AREF") (class "Default")
      (node (ref "U$4") (pin "4") (pinfunction "PA03/EINT3/VREFA/AIN1_4") (pintype "bidirectional"))
    )
    (net (code "9") (name "D+") (class "Default")
      (node (ref "U$4") (pin "34") (pinfunction "PA25/I13/SERCOM3+5.3/D+_34") (pintype "bidirectional"))
      (node (ref "X3") (pin "D+") (pinfunction "D+_D+") (pintype "bidirectional"))
    )
    (net (code "10") (name "D-") (class "Default")
      (node (ref "U$4") (pin "33") (pinfunction "PA24/I12/SERCOM3+5.2/D-_33") (pintype "bidirectional"))
      (node (ref "X3") (pin "D-") (pinfunction "D-_D-") (pintype "bidirectional"))
    )
    (net (code "11") (name "D2") (class "Default")
      (node (ref "U$4") (pin "23") (pinfunction "PA14/I14/SERCOM2+4.2_23") (pintype "bidirectional"))
    )
    (net (code "12") (name "D3") (class "Default")
      (node (ref "U$4") (pin "14") (pinfunction "PA09/I2C/I9/AIN17/SERCOM0+2.1/I2SMC_14") (pintype "bidirectional"))
    )
    (net (code "13") (name "D4") (class "Default")
      (node (ref "U$4") (pin "13") (pinfunction "PA08/I2C/AIN16/SERCOM0+2.0/I2SD1_13") (pintype "bidirectional"))
    )
    (net (code "14") (name "D5") (class "Default")
      (node (ref "U$4") (pin "24") (pinfunction "PA15/I15/SERCOM3+4.3_24") (pintype "bidirectional"))
    )
    (net (code "15") (name "D6") (class "Default")
      (node (ref "U$4") (pin "29") (pinfunction "PA20/I4/SERCOM3+5.2/I2SSC_29") (pintype "bidirectional"))
    )
    (net (code "16") (name "D7") (class "Default")
      (node (ref "U$4") (pin "30") (pinfunction "PA21/I5/SERCOM3+5.3/I2SFS0_30") (pintype "bidirectional"))
    )
    (net (code "17") (name "D8") (class "Default")
      (node (ref "U$4") (pin "11") (pinfunction "PA06/EINT6/AIN6/SERCOM0.2_11") (pintype "bidirectional"))
    )
    (net (code "18") (name "D9") (class "Default")
      (node (ref "U$4") (pin "12") (pinfunction "PA07/I7/AIN7/SERCOM0.3/I2SD0_12") (pintype "bidirectional"))
    )
    (net (code "19") (name "D10") (class "Default")
      (node (ref "U$4") (pin "27") (pinfunction "PA18/I2/SERCOM1+3.2_27") (pintype "bidirectional"))
    )
    (net (code "20") (name "D12") (class "Default")
      (node (ref "U$4") (pin "28") (pinfunction "PA19/I3/SERCOM1+3.3/I2SD0_28") (pintype "bidirectional"))
    )
    (net (code "21") (name "EN") (class "Default")
      (node (ref "P2") (pin "4") (pinfunction "4_4") (pintype "passive"))
      (node (ref "R45") (pin "2") (pinfunction "2_2") (pintype "passive"))
      (node (ref "U13") (pin "3") (pinfunction "EN_3") (pintype "input"))
    )
    (net (code "22") (name "GND") (class "Default")
      (node (ref "C1") (pin "2") (pinfunction "2_2") (pintype "passive"))
      (node (ref "C16") (pin "2") (pinfunction "2_2") (pintype "passive"))
      (node (ref "C17") (pin "2") (pinfunction "2_2") (pintype "passive"))
      (node (ref "C18") (pin "2") (pinfunction "2_2") (pintype "passive"))
      (node (ref "C19") (pin "2") (pinfunction "2_2") (pintype "passive"))
      (node (ref "C2") (pin "2") (pinfunction "2_2") (pintype "passive"))
      (node (ref "C20") (pin "2") (pinfunction "2_2") (pintype "passive"))
      (node (ref "C21") (pin "2") (pinfunction "2_2") (pintype "passive"))
      (node (ref "C22") (pin "2") (pinfunction "2_2") (pintype "passive"))
      (node (ref "C23") (pin "2") (pinfunction "2_2") (pintype "passive"))
      (node (ref "C24") (pin "2") (pinfunction "2_2") (pintype "passive"))
      (node (ref "C25") (pin "2") (pinfunction "2_2") (pintype "passive"))
      (node (ref "C26") (pin "2") (pinfunction "2_2") (pintype "passive"))
      (node (ref "C27") (pin "2") (pinfunction "2_2") (pintype "passive"))
      (node (ref "C28") (pin "2") (pinfunction "2_2") (pintype "passive"))
      (node (ref "C29") (pin "2") (pinfunction "2_2") (pintype "passive"))
      (node (ref "C30") (pin "2") (pinfunction "2_2") (pintype "passive"))
      (node (ref "C4") (pin "2") (pinfunction "2_2") (pintype "passive"))
      (node (ref "H1") (pin "B3,0") (pinfunction "MOUNT_B3,0") (pintype "passive"))
      (node (ref "H2") (pin "B3,0") (pinfunction "MOUNT_B3,0") (pintype "passive"))
      (node (ref "H3") (pin "B3,0") (pinfunction "MOUNT_B3,0") (pintype "passive"))
      (node (ref "H4") (pin "B3,0") (pinfunction "MOUNT_B3,0") (pintype "passive"))
      (node (ref "P2") (pin "1") (pinfunction "1_1") (pintype "passive"))
      (node (ref "PAD1") (pin "1") (pinfunction "P_1") (pintype "passive"))
      (node (ref "R26") (pin "1") (pinfunction "1_1") (pintype "passive"))
      (node (ref "R28") (pin "1") (pinfunction "1_1") (pintype "passive"))
      (node (ref "R30") (pin "1") (pinfunction "1_1") (pintype "passive"))
      (node (ref "R32") (pin "1") (pinfunction "1_1") (pintype "passive"))
      (node (ref "R34") (pin "1") (pinfunction "1_1") (pintype "passive"))
      (node (ref "R36") (pin "1") (pinfunction "1_1") (pintype "passive"))
      (node (ref "R40") (pin "1") (pinfunction "1_1") (pintype "passive"))
      (node (ref "R42") (pin "1") (pinfunction "1_1") (pintype "passive"))
      (node (ref "R44") (pin "1") (pinfunction "1_1") (pintype "passive"))
      (node (ref "U$4") (pin "18") (pinfunction "GND_18") (pintype "power_in"))
      (node (ref "U$4") (pin "35") (pinfunction "GND_35") (pintype "power_in"))
      (node (ref "U$4") (pin "42") (pinfunction "GND_42") (pintype "power_in"))
      (node (ref "U$4") (pin "5") (pinfunction "GNDA_5") (pintype "power_in"))
      (node (ref "U$4") (pin "THERMAL") (pinfunction "GND_THERMAL") (pintype "power_in"))
      (node (ref "U1") (pin "1") (pinfunction "GND_1") (pintype "power_in"))
      (node (ref "U1") (pin "10") (pinfunction "GND_10") (pintype "power_in"))
      (node (ref "U1") (pin "13") (pinfunction "GND_13") (pintype "power_in"))
      (node (ref "U1") (pin "16") (pinfunction "ADDR_16") (pintype "input"))
      (node (ref "U1") (pin "17") (pinfunction "GND_17") (pintype "power_in"))
      (node (ref "U1") (pin "18") (pinfunction "GND_18") (pintype "power_in"))
      (node (ref "U1") (pin "21") (pinfunction "EXP_21") (pintype "power_in"))
      (node (ref "U1") (pin "22") (pinfunction "EXP_22") (pintype "power_in"))
      (node (ref "U1") (pin "23") (pinfunction "EXP_23") (pintype "power_in"))
      (node (ref "U1") (pin "24") (pinfunction "EXP_24") (pintype "power_in"))
      (node (ref "U1") (pin "25") (pinfunction "EXP_25") (pintype "power_in"))
      (node (ref "U1") (pin "26") (pinfunction "EXP_26") (pintype "power_in"))
      (node (ref "U1") (pin "27") (pinfunction "EXP_27") (pintype "power_in"))
      (node (ref "U1") (pin "28") (pinfunction "EXP_28") (pintype "power_in"))
      (node (ref "U1") (pin "29") (pinfunction "EXP_29") (pintype "power_in"))
      (node (ref "U1") (pin "3") (pinfunction "GND_3") (pintype "power_in"))
      (node (ref "U1") (pin "30") (pinfunction "EXP_30") (pintype "power_in"))
      (node (ref "U1") (pin "5") (pinfunction "GND_5") (pintype "power_in"))
      (node (ref "U1") (pin "6") (pinfunction "GND_6") (pintype "power_in"))
      (node (ref "U1") (pin "7") (pinfunction "GND_7") (pintype "power_in"))
      (node (ref "U1") (pin "9") (pinfunction "GND_9") (pintype "power_in"))
      (node (ref "U10") (pin "1") (pinfunction "GND_1") (pintype "power_in"))
      (node (ref "U10") (pin "10") (pinfunction "GND_10") (pintype "power_in"))
      (node (ref "U10") (pin "13") (pinfunction "GND_13") (pintype "power_in"))
      (node (ref "U10") (pin "17") (pinfunction "GND_17") (pintype "power_in"))
      (node (ref "U10") (pin "18") (pinfunction "GND_18") (pintype "power_in"))
      (node (ref "U10") (pin "21") (pinfunction "EXP_21") (pintype "power_in"))
      (node (ref "U10") (pin "22") (pinfunction "EXP_22") (pintype "power_in"))
      (node (ref "U10") (pin "23") (pinfunction "EXP_23") (pintype "power_in"))
      (node (ref "U10") (pin "24") (pinfunction "EXP_24") (pintype "power_in"))
      (node (ref "U10") (pin "25") (pinfunction "EXP_25") (pintype "power_in"))
      (node (ref "U10") (pin "26") (pinfunction "EXP_26") (pintype "power_in"))
      (node (ref "U10") (pin "27") (pinfunction "EXP_27") (pintype "power_in"))
      (node (ref "U10") (pin "28") (pinfunction "EXP_28") (pintype "power_in"))
      (node (ref "U10") (pin "29") (pinfunction "EXP_29") (pintype "power_in"))
      (node (ref "U10") (pin "3") (pinfunction "GND_3") (pintype "power_in"))
      (node (ref "U10") (pin "30") (pinfunction "EXP_30") (pintype "power_in"))
      (node (ref "U10") (pin "5") (pinfunction "GND_5") (pintype "power_in"))
      (node (ref "U10") (pin "6") (pinfunction "GND_6") (pintype "power_in"))
      (node (ref "U10") (pin "7") (pinfunction "GND_7") (pintype "power_in"))
      (node (ref "U10") (pin "9") (pinfunction "GND_9") (pintype "power_in"))
      (node (ref "U11") (pin "1") (pinfunction "GND_1") (pintype "power_in"))
      (node (ref "U11") (pin "10") (pinfunction "GND_10") (pintype "power_in"))
      (node (ref "U11") (pin "13") (pinfunction "GND_13") (pintype "power_in"))
      (node (ref "U11") (pin "17") (pinfunction "GND_17") (pintype "power_in"))
      (node (ref "U11") (pin "18") (pinfunction "GND_18") (pintype "power_in"))
      (node (ref "U11") (pin "21") (pinfunction "EXP_21") (pintype "power_in"))
      (node (ref "U11") (pin "22") (pinfunction "EXP_22") (pintype "power_in"))
      (node (ref "U11") (pin "23") (pinfunction "EXP_23") (pintype "power_in"))
      (node (ref "U11") (pin "24") (pinfunction "EXP_24") (pintype "power_in"))
      (node (ref "U11") (pin "25") (pinfunction "EXP_25") (pintype "power_in"))
      (node (ref "U11") (pin "26") (pinfunction "EXP_26") (pintype "power_in"))
      (node (ref "U11") (pin "27") (pinfunction "EXP_27") (pintype "power_in"))
      (node (ref "U11") (pin "28") (pinfunction "EXP_28") (pintype "power_in"))
      (node (ref "U11") (pin "29") (pinfunction "EXP_29") (pintype "power_in"))
      (node (ref "U11") (pin "3") (pinfunction "GND_3") (pintype "power_in"))
      (node (ref "U11") (pin "30") (pinfunction "EXP_30") (pintype "power_in"))
      (node (ref "U11") (pin "5") (pinfunction "GND_5") (pintype "power_in"))
      (node (ref "U11") (pin "6") (pinfunction "GND_6") (pintype "power_in"))
      (node (ref "U11") (pin "7") (pinfunction "GND_7") (pintype "power_in"))
      (node (ref "U11") (pin "9") (pinfunction "GND_9") (pintype "power_in"))
      (node (ref "U12") (pin "1") (pinfunction "GND_1") (pintype "power_in"))
      (node (ref "U12") (pin "10") (pinfunction "GND_10") (pintype "power_in"))
      (node (ref "U12") (pin "13") (pinfunction "GND_13") (pintype "power_in"))
      (node (ref "U12") (pin "17") (pinfunction "GND_17") (pintype "power_in"))
      (node (ref "U12") (pin "18") (pinfunction "GND_18") (pintype "power_in"))
      (node (ref "U12") (pin "21") (pinfunction "EXP_21") (pintype "power_in"))
      (node (ref "U12") (pin "22") (pinfunction "EXP_22") (pintype "power_in"))
      (node (ref "U12") (pin "23") (pinfunction "EXP_23") (pintype "power_in"))
      (node (ref "U12") (pin "24") (pinfunction "EXP_24") (pintype "power_in"))
      (node (ref "U12") (pin "25") (pinfunction "EXP_25") (pintype "power_in"))
      (node (ref "U12") (pin "26") (pinfunction "EXP_26") (pintype "power_in"))
      (node (ref "U12") (pin "27") (pinfunction "EXP_27") (pintype "power_in"))
      (node (ref "U12") (pin "28") (pinfunction "EXP_28") (pintype "power_in"))
      (node (ref "U12") (pin "29") (pinfunction "EXP_29") (pintype "power_in"))
      (node (ref "U12") (pin "3") (pinfunction "GND_3") (pintype "power_in"))
      (node (ref "U12") (pin "30") (pinfunction "EXP_30") (pintype "power_in"))
      (node (ref "U12") (pin "5") (pinfunction "GND_5") (pintype "power_in"))
      (node (ref "U12") (pin "6") (pinfunction "GND_6") (pintype "power_in"))
      (node (ref "U12") (pin "7") (pinfunction "GND_7") (pintype "power_in"))
      (node (ref "U12") (pin "9") (pinfunction "GND_9") (pintype "power_in"))
      (node (ref "U13") (pin "2") (pinfunction "GND_2") (pintype "power_in"))
      (node (ref "U2") (pin "1") (pinfunction "GND_1") (pintype "power_in"))
      (node (ref "U2") (pin "10") (pinfunction "GND_10") (pintype "power_in"))
      (node (ref "U2") (pin "13") (pinfunction "GND_13") (pintype "power_in"))
      (node (ref "U2") (pin "17") (pinfunction "GND_17") (pintype "power_in"))
      (node (ref "U2") (pin "18") (pinfunction "GND_18") (pintype "power_in"))
      (node (ref "U2") (pin "21") (pinfunction "EXP_21") (pintype "power_in"))
      (node (ref "U2") (pin "22") (pinfunction "EXP_22") (pintype "power_in"))
      (node (ref "U2") (pin "23") (pinfunction "EXP_23") (pintype "power_in"))
      (node (ref "U2") (pin "24") (pinfunction "EXP_24") (pintype "power_in"))
      (node (ref "U2") (pin "25") (pinfunction "EXP_25") (pintype "power_in"))
      (node (ref "U2") (pin "26") (pinfunction "EXP_26") (pintype "power_in"))
      (node (ref "U2") (pin "27") (pinfunction "EXP_27") (pintype "power_in"))
      (node (ref "U2") (pin "28") (pinfunction "EXP_28") (pintype "power_in"))
      (node (ref "U2") (pin "29") (pinfunction "EXP_29") (pintype "power_in"))
      (node (ref "U2") (pin "3") (pinfunction "GND_3") (pintype "power_in"))
      (node (ref "U2") (pin "30") (pinfunction "EXP_30") (pintype "power_in"))
      (node (ref "U2") (pin "5") (pinfunction "GND_5") (pintype "power_in"))
      (node (ref "U2") (pin "6") (pinfunction "GND_6") (pintype "power_in"))
      (node (ref "U2") (pin "7") (pinfunction "GND_7") (pintype "power_in"))
      (node (ref "U2") (pin "9") (pinfunction "GND_9") (pintype "power_in"))
      (node (ref "U3") (pin "1") (pinfunction "GND_1") (pintype "power_in"))
      (node (ref "U3") (pin "10") (pinfunction "GND_10") (pintype "power_in"))
      (node (ref "U3") (pin "13") (pinfunction "GND_13") (pintype "power_in"))
      (node (ref "U3") (pin "17") (pinfunction "GND_17") (pintype "power_in"))
      (node (ref "U3") (pin "18") (pinfunction "GND_18") (pintype "power_in"))
      (node (ref "U3") (pin "21") (pinfunction "EXP_21") (pintype "power_in"))
      (node (ref "U3") (pin "22") (pinfunction "EXP_22") (pintype "power_in"))
      (node (ref "U3") (pin "23") (pinfunction "EXP_23") (pintype "power_in"))
      (node (ref "U3") (pin "24") (pinfunction "EXP_24") (pintype "power_in"))
      (node (ref "U3") (pin "25") (pinfunction "EXP_25") (pintype "power_in"))
      (node (ref "U3") (pin "26") (pinfunction "EXP_26") (pintype "power_in"))
      (node (ref "U3") (pin "27") (pinfunction "EXP_27") (pintype "power_in"))
      (node (ref "U3") (pin "28") (pinfunction "EXP_28") (pintype "power_in"))
      (node (ref "U3") (pin "29") (pinfunction "EXP_29") (pintype "power_in"))
      (node (ref "U3") (pin "3") (pinfunction "GND_3") (pintype "power_in"))
      (node (ref "U3") (pin "30") (pinfunction "EXP_30") (pintype "power_in"))
      (node (ref "U3") (pin "5") (pinfunction "GND_5") (pintype "power_in"))
      (node (ref "U3") (pin "6") (pinfunction "GND_6") (pintype "power_in"))
      (node (ref "U3") (pin "7") (pinfunction "GND_7") (pintype "power_in"))
      (node (ref "U3") (pin "9") (pinfunction "GND_9") (pintype "power_in"))
      (node (ref "U4") (pin "1") (pinfunction "GND_1") (pintype "power_in"))
      (node (ref "U4") (pin "10") (pinfunction "GND_10") (pintype "power_in"))
      (node (ref "U4") (pin "13") (pinfunction "GND_13") (pintype "power_in"))
      (node (ref "U4") (pin "17") (pinfunction "GND_17") (pintype "power_in"))
      (node (ref "U4") (pin "18") (pinfunction "GND_18") (pintype "power_in"))
      (node (ref "U4") (pin "21") (pinfunction "EXP_21") (pintype "power_in"))
      (node (ref "U4") (pin "22") (pinfunction "EXP_22") (pintype "power_in"))
      (node (ref "U4") (pin "23") (pinfunction "EXP_23") (pintype "power_in"))
      (node (ref "U4") (pin "24") (pinfunction "EXP_24") (pintype "power_in"))
      (node (ref "U4") (pin "25") (pinfunction "EXP_25") (pintype "power_in"))
      (node (ref "U4") (pin "26") (pinfunction "EXP_26") (pintype "power_in"))
      (node (ref "U4") (pin "27") (pinfunction "EXP_27") (pintype "power_in"))
      (node (ref "U4") (pin "28") (pinfunction "EXP_28") (pintype "power_in"))
      (node (ref "U4") (pin "29") (pinfunction "EXP_29") (pintype "power_in"))
      (node (ref "U4") (pin "3") (pinfunction "GND_3") (pintype "power_in"))
      (node (ref "U4") (pin "30") (pinfunction "EXP_30") (pintype "power_in"))
      (node (ref "U4") (pin "5") (pinfunction "GND_5") (pintype "power_in"))
      (node (ref "U4") (pin "6") (pinfunction "GND_6") (pintype "power_in"))
      (node (ref "U4") (pin "7") (pinfunction "GND_7") (pintype "power_in"))
      (node (ref "U4") (pin "9") (pinfunction "GND_9") (pintype "power_in"))
      (node (ref "U5") (pin "1") (pinfunction "GND_1") (pintype "power_in"))
      (node (ref "U5") (pin "10") (pinfunction "GND_10") (pintype "power_in"))
      (node (ref "U5") (pin "13") (pinfunction "GND_13") (pintype "power_in"))
      (node (ref "U5") (pin "17") (pinfunction "GND_17") (pintype "power_in"))
      (node (ref "U5") (pin "18") (pinfunction "GND_18") (pintype "power_in"))
      (node (ref "U5") (pin "21") (pinfunction "EXP_21") (pintype "power_in"))
      (node (ref "U5") (pin "22") (pinfunction "EXP_22") (pintype "power_in"))
      (node (ref "U5") (pin "23") (pinfunction "EXP_23") (pintype "power_in"))
      (node (ref "U5") (pin "24") (pinfunction "EXP_24") (pintype "power_in"))
      (node (ref "U5") (pin "25") (pinfunction "EXP_25") (pintype "power_in"))
      (node (ref "U5") (pin "26") (pinfunction "EXP_26") (pintype "power_in"))
      (node (ref "U5") (pin "27") (pinfunction "EXP_27") (pintype "power_in"))
      (node (ref "U5") (pin "28") (pinfunction "EXP_28") (pintype "power_in"))
      (node (ref "U5") (pin "29") (pinfunction "EXP_29") (pintype "power_in"))
      (node (ref "U5") (pin "3") (pinfunction "GND_3") (pintype "power_in"))
      (node (ref "U5") (pin "30") (pinfunction "EXP_30") (pintype "power_in"))
      (node (ref "U5") (pin "5") (pinfunction "GND_5") (pintype "power_in"))
      (node (ref "U5") (pin "6") (pinfunction "GND_6") (pintype "power_in"))
      (node (ref "U5") (pin "7") (pinfunction "GND_7") (pintype "power_in"))
      (node (ref "U5") (pin "9") (pinfunction "GND_9") (pintype "power_in"))
      (node (ref "U6") (pin "1") (pinfunction "GND_1") (pintype "power_in"))
      (node (ref "U6") (pin "10") (pinfunction "GND_10") (pintype "power_in"))
      (node (ref "U6") (pin "13") (pinfunction "GND_13") (pintype "power_in"))
      (node (ref "U6") (pin "17") (pinfunction "GND_17") (pintype "power_in"))
      (node (ref "U6") (pin "18") (pinfunction "GND_18") (pintype "power_in"))
      (node (ref "U6") (pin "21") (pinfunction "EXP_21") (pintype "power_in"))
      (node (ref "U6") (pin "22") (pinfunction "EXP_22") (pintype "power_in"))
      (node (ref "U6") (pin "23") (pinfunction "EXP_23") (pintype "power_in"))
      (node (ref "U6") (pin "24") (pinfunction "EXP_24") (pintype "power_in"))
      (node (ref "U6") (pin "25") (pinfunction "EXP_25") (pintype "power_in"))
      (node (ref "U6") (pin "26") (pinfunction "EXP_26") (pintype "power_in"))
      (node (ref "U6") (pin "27") (pinfunction "EXP_27") (pintype "power_in"))
      (node (ref "U6") (pin "28") (pinfunction "EXP_28") (pintype "power_in"))
      (node (ref "U6") (pin "29") (pinfunction "EXP_29") (pintype "power_in"))
      (node (ref "U6") (pin "3") (pinfunction "GND_3") (pintype "power_in"))
      (node (ref "U6") (pin "30") (pinfunction "EXP_30") (pintype "power_in"))
      (node (ref "U6") (pin "5") (pinfunction "GND_5") (pintype "power_in"))
      (node (ref "U6") (pin "6") (pinfunction "GND_6") (pintype "power_in"))
      (node (ref "U6") (pin "7") (pinfunction "GND_7") (pintype "power_in"))
      (node (ref "U6") (pin "9") (pinfunction "GND_9") (pintype "power_in"))
      (node (ref "U7") (pin "1") (pinfunction "GND_1") (pintype "power_in"))
      (node (ref "U7") (pin "10") (pinfunction "GND_10") (pintype "power_in"))
      (node (ref "U7") (pin "13") (pinfunction "GND_13") (pintype "power_in"))
      (node (ref "U7") (pin "16") (pinfunction "ADDR_16") (pintype "input"))
      (node (ref "U7") (pin "17") (pinfunction "GND_17") (pintype "power_in"))
      (node (ref "U7") (pin "18") (pinfunction "GND_18") (pintype "power_in"))
      (node (ref "U7") (pin "21") (pinfunction "EXP_21") (pintype "power_in"))
      (node (ref "U7") (pin "22") (pinfunction "EXP_22") (pintype "power_in"))
      (node (ref "U7") (pin "23") (pinfunction "EXP_23") (pintype "power_in"))
      (node (ref "U7") (pin "24") (pinfunction "EXP_24") (pintype "power_in"))
      (node (ref "U7") (pin "25") (pinfunction "EXP_25") (pintype "power_in"))
      (node (ref "U7") (pin "26") (pinfunction "EXP_26") (pintype "power_in"))
      (node (ref "U7") (pin "27") (pinfunction "EXP_27") (pintype "power_in"))
      (node (ref "U7") (pin "28") (pinfunction "EXP_28") (pintype "power_in"))
      (node (ref "U7") (pin "29") (pinfunction "EXP_29") (pintype "power_in"))
      (node (ref "U7") (pin "3") (pinfunction "GND_3") (pintype "power_in"))
      (node (ref "U7") (pin "30") (pinfunction "EXP_30") (pintype "power_in"))
      (node (ref "U7") (pin "5") (pinfunction "GND_5") (pintype "power_in"))
      (node (ref "U7") (pin "6") (pinfunction "GND_6") (pintype "power_in"))
      (node (ref "U7") (pin "7") (pinfunction "GND_7") (pintype "power_in"))
      (node (ref "U7") (pin "9") (pinfunction "GND_9") (pintype "power_in"))
      (node (ref "U8") (pin "1") (pinfunction "GND_1") (pintype "power_in"))
      (node (ref "U8") (pin "10") (pinfunction "GND_10") (pintype "power_in"))
      (node (ref "U8") (pin "13") (pinfunction "GND_13") (pintype "power_in"))
      (node (ref "U8") (pin "17") (pinfunction "GND_17") (pintype "power_in"))
      (node (ref "U8") (pin "18") (pinfunction "GND_18") (pintype "power_in"))
      (node (ref "U8") (pin "21") (pinfunction "EXP_21") (pintype "power_in"))
      (node (ref "U8") (pin "22") (pinfunction "EXP_22") (pintype "power_in"))
      (node (ref "U8") (pin "23") (pinfunction "EXP_23") (pintype "power_in"))
      (node (ref "U8") (pin "24") (pinfunction "EXP_24") (pintype "power_in"))
      (node (ref "U8") (pin "25") (pinfunction "EXP_25") (pintype "power_in"))
      (node (ref "U8") (pin "26") (pinfunction "EXP_26") (pintype "power_in"))
      (node (ref "U8") (pin "27") (pinfunction "EXP_27") (pintype "power_in"))
      (node (ref "U8") (pin "28") (pinfunction "EXP_28") (pintype "power_in"))
      (node (ref "U8") (pin "29") (pinfunction "EXP_29") (pintype "power_in"))
      (node (ref "U8") (pin "3") (pinfunction "GND_3") (pintype "power_in"))
      (node (ref "U8") (pin "30") (pinfunction "EXP_30") (pintype "power_in"))
      (node (ref "U8") (pin "5") (pinfunction "GND_5") (pintype "power_in"))
      (node (ref "U8") (pin "6") (pinfunction "GND_6") (pintype "power_in"))
      (node (ref "U8") (pin "7") (pinfunction "GND_7") (pintype "power_in"))
      (node (ref "U8") (pin "9") (pinfunction "GND_9") (pintype "power_in"))
      (node (ref "U9") (pin "1") (pinfunction "GND_1") (pintype "power_in"))
      (node (ref "U9") (pin "10") (pinfunction "GND_10") (pintype "power_in"))
      (node (ref "U9") (pin "13") (pinfunction "GND_13") (pintype "power_in"))
      (node (ref "U9") (pin "17") (pinfunction "GND_17") (pintype "power_in"))
      (node (ref "U9") (pin "18") (pinfunction "GND_18") (pintype "power_in"))
      (node (ref "U9") (pin "21") (pinfunction "EXP_21") (pintype "power_in"))
      (node (ref "U9") (pin "22") (pinfunction "EXP_22") (pintype "power_in"))
      (node (ref "U9") (pin "23") (pinfunction "EXP_23") (pintype "power_in"))
      (node (ref "U9") (pin "24") (pinfunction "EXP_24") (pintype "power_in"))
      (node (ref "U9") (pin "25") (pinfunction "EXP_25") (pintype "power_in"))
      (node (ref "U9") (pin "26") (pinfunction "EXP_26") (pintype "power_in"))
      (node (ref "U9") (pin "27") (pinfunction "EXP_27") (pintype "power_in"))
      (node (ref "U9") (pin "28") (pinfunction "EXP_28") (pintype "power_in"))
      (node (ref "U9") (pin "29") (pinfunction "EXP_29") (pintype "power_in"))
      (node (ref "U9") (pin "3") (pinfunction "GND_3") (pintype "power_in"))
      (node (ref "U9") (pin "30") (pinfunction "EXP_30") (pintype "power_in"))
      (node (ref "U9") (pin "5") (pinfunction "GND_5") (pintype "power_in"))
      (node (ref "U9") (pin "6") (pinfunction "GND_6") (pintype "power_in"))
      (node (ref "U9") (pin "7") (pinfunction "GND_7") (pintype "power_in"))
      (node (ref "U9") (pin "9") (pinfunction "GND_9") (pintype "power_in"))
      (node (ref "X3") (pin "BASE@1") (pinfunction "GND_BASE@1") (pintype "power_in"))
      (node (ref "X3") (pin "BASE@2") (pinfunction "GND_BASE@2") (pintype "power_in"))
      (node (ref "X3") (pin "GND") (pinfunction "GND_GND") (pintype "power_in"))
      (node (ref "X3") (pin "SPRT@1") (pinfunction "GND_SPRT@1") (pintype "power_in"))
      (node (ref "X3") (pin "SPRT@2") (pinfunction "GND_SPRT@2") (pintype "power_in"))
      (node (ref "X3") (pin "SPRT@3") (pinfunction "GND_SPRT@3") (pintype "power_in"))
      (node (ref "X3") (pin "SPRT@4") (pinfunction "GND_SPRT@4") (pintype "power_in"))
    )
    (net (code "23") (name "MISO") (class "Default")
      (node (ref "U$4") (pin "21") (pinfunction "PA12/I12/I2C/SERCOM2+4.0_21") (pintype "bidirectional"))
    )
    (net (code "24") (name "MOSI") (class "Default")
      (node (ref "U$4") (pin "19") (pinfunction "PB10/I10/SERCOM4.2/I2SMC_19") (pintype "bidirectional"))
    )
    (net (code "25") (name "Net-(J1-Pad1)") (class "Default")
      (node (ref "J1") (pin "1") (pinfunction "1_1") (pintype "passive"))
      (node (ref "R13") (pin "1") (pinfunction "1_1") (pintype "passive"))
    )
    (net (code "26") (name "Net-(J1-Pad2)") (class "Default")
      (node (ref "J1") (pin "2") (pinfunction "2_2") (pintype "passive"))
      (node (ref "R14") (pin "1") (pinfunction "1_1") (pintype "passive"))
    )
    (net (code "27") (name "Net-(J2-Pad1)") (class "Default")
      (node (ref "J2") (pin "1") (pinfunction "1_1") (pintype "passive"))
      (node (ref "R15") (pin "1") (pinfunction "1_1") (pintype "passive"))
    )
    (net (code "28") (name "Net-(J2-Pad2)") (class "Default")
      (node (ref "J2") (pin "2") (pinfunction "2_2") (pintype "passive"))
      (node (ref "R16") (pin "1") (pinfunction "1_1") (pintype "passive"))
    )
    (net (code "29") (name "Net-(J3-Pad1)") (class "Default")
      (node (ref "J3") (pin "1") (pinfunction "1_1") (pintype "passive"))
      (node (ref "R17") (pin "1") (pinfunction "1_1") (pintype "passive"))
    )
    (net (code "30") (name "Net-(J3-Pad2)") (class "Default")
      (node (ref "J3") (pin "2") (pinfunction "2_2") (pintype "passive"))
      (node (ref "R18") (pin "1") (pinfunction "1_1") (pintype "passive"))
    )
    (net (code "31") (name "Net-(J4-Pad1)") (class "Default")
      (node (ref "J4") (pin "1") (pinfunction "1_1") (pintype "passive"))
      (node (ref "R20") (pin "1") (pinfunction "1_1") (pintype "passive"))
    )
    (net (code "32") (name "Net-(J4-Pad2)") (class "Default")
      (node (ref "J4") (pin "2") (pinfunction "2_2") (pintype "passive"))
      (node (ref "R19") (pin "1") (pinfunction "1_1") (pintype "passive"))
    )
    (net (code "33") (name "Net-(J5-Pad1)") (class "Default")
      (node (ref "J5") (pin "1") (pinfunction "1_1") (pintype "passive"))
      (node (ref "R22") (pin "1") (pinfunction "1_1") (pintype "passive"))
    )
    (net (code "34") (name "Net-(J5-Pad2)") (class "Default")
      (node (ref "J5") (pin "2") (pinfunction "2_2") (pintype "passive"))
      (node (ref "R21") (pin "1") (pinfunction "1_1") (pintype "passive"))
    )
    (net (code "35") (name "Net-(J6-Pad1)") (class "Default")
      (node (ref "J6") (pin "1") (pinfunction "1_1") (pintype "passive"))
      (node (ref "R1") (pin "1") (pinfunction "1_1") (pintype "passive"))
    )
    (net (code "36") (name "Net-(J6-Pad2)") (class "Default")
      (node (ref "J6") (pin "2") (pinfunction "2_2") (pintype "passive"))
      (node (ref "R2") (pin "1") (pinfunction "1_1") (pintype "passive"))
    )
    (net (code "37") (name "Net-(J7-Pad1)") (class "Default")
      (node (ref "J7") (pin "1") (pinfunction "1_1") (pintype "passive"))
      (node (ref "R12") (pin "1") (pinfunction "1_1") (pintype "passive"))
    )
    (net (code "38") (name "Net-(J7-Pad2)") (class "Default")
      (node (ref "J7") (pin "2") (pinfunction "2_2") (pintype "passive"))
      (node (ref "R11") (pin "1") (pinfunction "1_1") (pintype "passive"))
    )
    (net (code "39") (name "Net-(J8-Pad1)") (class "Default")
      (node (ref "J8") (pin "1") (pinfunction "1_1") (pintype "passive"))
      (node (ref "R9") (pin "1") (pinfunction "1_1") (pintype "passive"))
    )
    (net (code "40") (name "Net-(J8-Pad2)") (class "Default")
      (node (ref "J8") (pin "2") (pinfunction "2_2") (pintype "passive"))
      (node (ref "R10") (pin "1") (pinfunction "1_1") (pintype "passive"))
    )
    (net (code "41") (name "Net-(J9-Pad1)") (class "Default")
      (node (ref "J9") (pin "1") (pinfunction "1_1") (pintype "passive"))
      (node (ref "R3") (pin "1") (pinfunction "1_1") (pintype "passive"))
    )
    (net (code "42") (name "Net-(J9-Pad2)") (class "Default")
      (node (ref "J9") (pin "2") (pinfunction "2_2") (pintype "passive"))
      (node (ref "R4") (pin "1") (pinfunction "1_1") (pintype "passive"))
    )
    (net (code "43") (name "Net-(J10-Pad1)") (class "Default")
      (node (ref "J10") (pin "1") (pinfunction "1_1") (pintype "passive"))
      (node (ref "R5") (pin "1") (pinfunction "1_1") (pintype "passive"))
    )
    (net (code "44") (name "Net-(J10-Pad2)") (class "Default")
      (node (ref "J10") (pin "2") (pinfunction "2_2") (pintype "passive"))
      (node (ref "R6") (pin "1") (pinfunction "1_1") (pintype "passive"))
    )
    (net (code "45") (name "Net-(J11-Pad1)") (class "Default")
      (node (ref "J11") (pin "1") (pinfunction "1_1") (pintype "passive"))
      (node (ref "R7") (pin "1") (pinfunction "1_1") (pintype "passive"))
    )
    (net (code "46") (name "Net-(J11-Pad2)") (class "Default")
      (node (ref "J11") (pin "2") (pinfunction "2_2") (pintype "passive"))
      (node (ref "R8") (pin "1") (pinfunction "1_1") (pintype "passive"))
    )
    (net (code "47") (name "Net-(J12-Pad1)") (class "Default")
      (node (ref "J12") (pin "1") (pinfunction "1_1") (pintype "passive"))
      (node (ref "R23") (pin "1") (pinfunction "1_1") (pintype "passive"))
    )
    (net (code "48") (name "Net-(J12-Pad2)") (class "Default")
      (node (ref "J12") (pin "2") (pinfunction "2_2") (pintype "passive"))
      (node (ref "R24") (pin "1") (pinfunction "1_1") (pintype "passive"))
    )
    (net (code "49") (name "Net-(U$4-PA00{slash}EINT0{slash}SERCOM1.0)") (class "Default")
      (node (ref "C2") (pin "1") (pinfunction "1_1") (pintype "passive"))
      (node (ref "U$4") (pin "1") (pinfunction "PA00/EINT0/SERCOM1.0_1") (pintype "bidirectional"))
      (node (ref "X2") (pin "P$1") (pinfunction "P$1_P$1") (pintype "bidirectional"))
    )
    (net (code "50") (name "Net-(U$4-PA01{slash}EINT1{slash}SERCOM1.1)") (class "Default")
      (node (ref "C4") (pin "1") (pinfunction "1_1") (pintype "passive"))
      (node (ref "U$4") (pin "2") (pinfunction "PA01/EINT1/SERCOM1.1_2") (pintype "bidirectional"))
      (node (ref "X2") (pin "P$2") (pinfunction "P$2_P$2") (pintype "bidirectional"))
    )
    (net (code "51") (name "Net-(U$4-VDDCORE)") (class "Default")
      (node (ref "C1") (pin "1") (pinfunction "1_1") (pintype "passive"))
      (node (ref "U$4") (pin "43") (pinfunction "VDDCORE_43") (pintype "power_in"))
    )
    (net (code "52") (name "Net-(U1-VIN+)") (class "Default")
      (node (ref "C3") (pin "1") (pinfunction "1_1") (pintype "passive"))
      (node (ref "R1") (pin "2") (pinfunction "2_2") (pintype "passive"))
      (node (ref "U1") (pin "2") (pinfunction "VIN+_2") (pintype "input"))
    )
    (net (code "53") (name "Net-(U1-VIN-)") (class "Default")
      (node (ref "C3") (pin "2") (pinfunction "2_2") (pintype "passive"))
      (node (ref "R2") (pin "2") (pinfunction "2_2") (pintype "passive"))
      (node (ref "U1") (pin "4") (pinfunction "VIN-_4") (pintype "input"))
    )
    (net (code "54") (name "Net-(U2-ADDR)") (class "Default")
      (node (ref "R29") (pin "2") (pinfunction "2_2") (pintype "passive"))
      (node (ref "R30") (pin "2") (pinfunction "2_2") (pintype "passive"))
      (node (ref "U2") (pin "16") (pinfunction "ADDR_16") (pintype "input"))
    )
    (net (code "55") (name "Net-(U2-VIN+)") (class "Default")
      (node (ref "C5") (pin "1") (pinfunction "1_1") (pintype "passive"))
      (node (ref "R3") (pin "2") (pinfunction "2_2") (pintype "passive"))
      (node (ref "U2") (pin "2") (pinfunction "VIN+_2") (pintype "input"))
    )
    (net (code "56") (name "Net-(U2-VIN-)") (class "Default")
      (node (ref "C5") (pin "2") (pinfunction "2_2") (pintype "passive"))
      (node (ref "R4") (pin "2") (pinfunction "2_2") (pintype "passive"))
      (node (ref "U2") (pin "4") (pinfunction "VIN-_4") (pintype "input"))
    )
    (net (code "57") (name "Net-(U3-ADDR)") (class "Default")
      (node (ref "R27") (pin "2") (pinfunction "2_2") (pintype "passive"))
      (node (ref "R28") (pin "2") (pinfunction "2_2") (pintype "passive"))
      (node (ref "U3") (pin "16") (pinfunction "ADDR_16") (pintype "input"))
    )
    (net (code "58") (name "Net-(U3-VIN+)") (class "Default")
      (node (ref "C6") (pin "1") (pinfunction "1_1") (pintype "passive"))
      (node (ref "R12") (pin "2") (pinfunction "2_2") (pintype "passive"))
      (node (ref "U3") (pin "2") (pinfunction "VIN+_2") (pintype "input"))
    )
    (net (code "59") (name "Net-(U3-VIN-)") (class "Default")
      (node (ref "C6") (pin "2") (pinfunction "2_2") (pintype "passive"))
      (node (ref "R11") (pin "2") (pinfunction "2_2") (pintype "passive"))
      (node (ref "U3") (pin "4") (pinfunction "VIN-_4") (pintype "input"))
    )
    (net (code "60") (name "Net-(U4-ADDR)") (class "Default")
      (node (ref "R35") (pin "2") (pinfunction "2_2") (pintype "passive"))
      (node (ref "R36") (pin "2") (pinfunction "2_2") (pintype "passive"))
      (node (ref "U4") (pin "16") (pinfunction "ADDR_16") (pintype "input"))
    )
    (net (code "61") (name "Net-(U4-VIN+)") (class "Default")
      (node (ref "C10") (pin "1") (pinfunction "1_1") (pintype "passive"))
      (node (ref "R13") (pin "2") (pinfunction "2_2") (pintype "passive"))
      (node (ref "U4") (pin "2") (pinfunction "VIN+_2") (pintype "input"))
    )
    (net (code "62") (name "Net-(U4-VIN-)") (class "Default")
      (node (ref "C10") (pin "2") (pinfunction "2_2") (pintype "passive"))
      (node (ref "R14") (pin "2") (pinfunction "2_2") (pintype "passive"))
      (node (ref "U4") (pin "4") (pinfunction "VIN-_4") (pintype "input"))
    )
    (net (code "63") (name "Net-(U5-ADDR)") (class "Default")
      (node (ref "R25") (pin "2") (pinfunction "2_2") (pintype "passive"))
      (node (ref "R26") (pin "2") (pinfunction "2_2") (pintype "passive"))
      (node (ref "U5") (pin "16") (pinfunction "ADDR_16") (pintype "input"))
    )
    (net (code "64") (name "Net-(U5-VIN+)") (class "Default")
      (node (ref "C11") (pin "1") (pinfunction "1_1") (pintype "passive"))
      (node (ref "R15") (pin "2") (pinfunction "2_2") (pintype "passive"))
      (node (ref "U5") (pin "2") (pinfunction "VIN+_2") (pintype "input"))
    )
    (net (code "65") (name "Net-(U5-VIN-)") (class "Default")
      (node (ref "C11") (pin "2") (pinfunction "2_2") (pintype "passive"))
      (node (ref "R16") (pin "2") (pinfunction "2_2") (pintype "passive"))
      (node (ref "U5") (pin "4") (pinfunction "VIN-_4") (pintype "input"))
    )
    (net (code "66") (name "Net-(U6-ADDR)") (class "Default")
      (node (ref "R33") (pin "2") (pinfunction "2_2") (pintype "passive"))
      (node (ref "R34") (pin "2") (pinfunction "2_2") (pintype "passive"))
      (node (ref "U6") (pin "16") (pinfunction "ADDR_16") (pintype "input"))
    )
    (net (code "67") (name "Net-(U6-VIN+)") (class "Default")
      (node (ref "C8") (pin "1") (pinfunction "1_1") (pintype "passive"))
      (node (ref "R5") (pin "2") (pinfunction "2_2") (pintype "passive"))
      (node (ref "U6") (pin "2") (pinfunction "VIN+_2") (pintype "input"))
    )
    (net (code "68") (name "Net-(U6-VIN-)") (class "Default")
      (node (ref "C8") (pin "2") (pinfunction "2_2") (pintype "passive"))
      (node (ref "R6") (pin "2") (pinfunction "2_2") (pintype "passive"))
      (node (ref "U6") (pin "4") (pinfunction "VIN-_4") (pintype "input"))
    )
    (net (code "69") (name "Net-(U7-VIN+)") (class "Default")
      (node (ref "C12") (pin "1") (pinfunction "1_1") (pintype "passive"))
      (node (ref "R20") (pin "2") (pinfunction "2_2") (pintype "passive"))
      (node (ref "U7") (pin "2") (pinfunction "VIN+_2") (pintype "input"))
    )
    (net (code "70") (name "Net-(U7-VIN-)") (class "Default")
      (node (ref "C12") (pin "2") (pinfunction "2_2") (pintype "passive"))
      (node (ref "R19") (pin "2") (pinfunction "2_2") (pintype "passive"))
      (node (ref "U7") (pin "4") (pinfunction "VIN-_4") (pintype "input"))
    )
    (net (code "71") (name "Net-(U8-VIN+)") (class "Default")
      (node (ref "C15") (pin "1") (pinfunction "1_1") (pintype "passive"))
      (node (ref "R23") (pin "2") (pinfunction "2_2") (pintype "passive"))
      (node (ref "U8") (pin "2") (pinfunction "VIN+_2") (pintype "input"))
    )
    (net (code "72") (name "Net-(U8-VIN-)") (class "Default")
      (node (ref "C15") (pin "2") (pinfunction "2_2") (pintype "passive"))
      (node (ref "R24") (pin "2") (pinfunction "2_2") (pintype "passive"))
      (node (ref "U8") (pin "4") (pinfunction "VIN-_4") (pintype "input"))
    )
    (net (code "73") (name "Net-(U9-ADDR)") (class "Default")
      (node (ref "R31") (pin "2") (pinfunction "2_2") (pintype "passive"))
      (node (ref "R32") (pin "2") (pinfunction "2_2") (pintype "passive"))
      (node (ref "U9") (pin "16") (pinfunction "ADDR_16") (pintype "input"))
    )
    (net (code "74") (name "Net-(U9-VIN+)") (class "Default")
      (node (ref "C13") (pin "1") (pinfunction "1_1") (pintype "passive"))
      (node (ref "R17") (pin "2") (pinfunction "2_2") (pintype "passive"))
      (node (ref "U9") (pin "2") (pinfunction "VIN+_2") (pintype "input"))
    )
    (net (code "75") (name "Net-(U9-VIN-)") (class "Default")
      (node (ref "C13") (pin "2") (pinfunction "2_2") (pintype "passive"))
      (node (ref "R18") (pin "2") (pinfunction "2_2") (pintype "passive"))
      (node (ref "U9") (pin "4") (pinfunction "VIN-_4") (pintype "input"))
    )
    (net (code "76") (name "Net-(U10-ADDR)") (class "Default")
      (node (ref "R39") (pin "2") (pinfunction "2_2") (pintype "passive"))
      (node (ref "R40") (pin "2") (pinfunction "2_2") (pintype "passive"))
      (node (ref "U10") (pin "16") (pinfunction "ADDR_16") (pintype "input"))
    )
    (net (code "77") (name "Net-(U10-VIN+)") (class "Default")
      (node (ref "C14") (pin "1") (pinfunction "1_1") (pintype "passive"))
      (node (ref "R22") (pin "2") (pinfunction "2_2") (pintype "passive"))
      (node (ref "U10") (pin "2") (pinfunction "VIN+_2") (pintype "input"))
    )
    (net (code "78") (name "Net-(U10-VIN-)") (class "Default")
      (node (ref "C14") (pin "2") (pinfunction "2_2") (pintype "passive"))
      (node (ref "R21") (pin "2") (pinfunction "2_2") (pintype "passive"))
      (node (ref "U10") (pin "4") (pinfunction "VIN-_4") (pintype "input"))
    )
    (net (code "79") (name "Net-(U11-ADDR)") (class "Default")
      (node (ref "R41") (pin "2") (pinfunction "2_2") (pintype "passive"))
      (node (ref "R42") (pin "2") (pinfunction "2_2") (pintype "passive"))
      (node (ref "U11") (pin "16") (pinfunction "ADDR_16") (pintype "input"))
    )
    (net (code "80") (name "Net-(U11-VIN+)") (class "Default")
      (node (ref "C7") (pin "1") (pinfunction "1_1") (pintype "passive"))
      (node (ref "R9") (pin "2") (pinfunction "2_2") (pintype "passive"))
      (node (ref "U11") (pin "2") (pinfunction "VIN+_2") (pintype "input"))
    )
    (net (code "81") (name "Net-(U11-VIN-)") (class "Default")
      (node (ref "C7") (pin "2") (pinfunction "2_2") (pintype "passive"))
      (node (ref "R10") (pin "2") (pinfunction "2_2") (pintype "passive"))
      (node (ref "U11") (pin "4") (pinfunction "VIN-_4") (pintype "input"))
    )
    (net (code "82") (name "Net-(U12-ADDR)") (class "Default")
      (node (ref "R43") (pin "2") (pinfunction "2_2") (pintype "passive"))
      (node (ref "R44") (pin "2") (pinfunction "2_2") (pintype "passive"))
      (node (ref "U12") (pin "16") (pinfunction "ADDR_16") (pintype "input"))
    )
    (net (code "83") (name "Net-(U12-VIN+)") (class "Default")
      (node (ref "C9") (pin "1") (pinfunction "1_1") (pintype "passive"))
      (node (ref "R7") (pin "2") (pinfunction "2_2") (pintype "passive"))
      (node (ref "U12") (pin "2") (pinfunction "VIN+_2") (pintype "input"))
    )
    (net (code "84") (name "Net-(U12-VIN-)") (class "Default")
      (node (ref "C9") (pin "2") (pinfunction "2_2") (pintype "passive"))
      (node (ref "R8") (pin "2") (pinfunction "2_2") (pintype "passive"))
      (node (ref "U12") (pin "4") (pinfunction "VIN-_4") (pintype "input"))
    )
    (net (code "85") (name "RX") (class "Default")
      (node (ref "P2") (pin "3") (pinfunction "3_3") (pintype "passive"))
      (node (ref "U$4") (pin "16") (pinfunction "PA11/I11/AIN19/SERCOM0+2.3/I2SF0_16") (pintype "bidirectional"))
    )
    (net (code "86") (name "SCK") (class "Default")
      (node (ref "U$4") (pin "20") (pinfunction "PB11/I11/SERCOM4.3/I2SCL_20") (pintype "bidirectional"))
    )
    (net (code "87") (name "SCL1") (class "Default")
      (node (ref "R38") (pin "2") (pinfunction "2_2") (pintype "passive"))
      (node (ref "U$4") (pin "32") (pinfunction "PA23/I2C/I7/SERCOM3+5.1/SOF_32") (pintype "bidirectional"))
      (node (ref "U1") (pin "19") (pinfunction "SCL_19") (pintype "input"))
      (node (ref "U2") (pin "19") (pinfunction "SCL_19") (pintype "input"))
      (node (ref "U3") (pin "19") (pinfunction "SCL_19") (pintype "input"))
      (node (ref "U4") (pin "19") (pinfunction "SCL_19") (pintype "input"))
      (node (ref "U5") (pin "19") (pinfunction "SCL_19") (pintype "input"))
      (node (ref "U6") (pin "19") (pinfunction "SCL_19") (pintype "input"))
    )
    (net (code "88") (name "SCL2") (class "Default")
      (node (ref "R47") (pin "2") (pinfunction "2_2") (pintype "passive"))
      (node (ref "U$4") (pin "26") (pinfunction "PA17/I2C/I1/SERCOM1+3.1_26") (pintype "bidirectional"))
      (node (ref "U10") (pin "19") (pinfunction "SCL_19") (pintype "input"))
      (node (ref "U11") (pin "19") (pinfunction "SCL_19") (pintype "input"))
      (node (ref "U12") (pin "19") (pinfunction "SCL_19") (pintype "input"))
      (node (ref "U7") (pin "19") (pinfunction "SCL_19") (pintype "input"))
      (node (ref "U8") (pin "19") (pinfunction "SCL_19") (pintype "input"))
      (node (ref "U9") (pin "19") (pinfunction "SCL_19") (pintype "input"))
    )
    (net (code "89") (name "SDA1") (class "Default")
      (node (ref "R37") (pin "2") (pinfunction "2_2") (pintype "passive"))
      (node (ref "U$4") (pin "31") (pinfunction "PA22/I2C/I6/SERCOM3+5.0_31") (pintype "bidirectional"))
      (node (ref "U1") (pin "20") (pinfunction "SDA_20") (pintype "bidirectional"))
      (node (ref "U2") (pin "20") (pinfunction "SDA_20") (pintype "bidirectional"))
      (node (ref "U3") (pin "20") (pinfunction "SDA_20") (pintype "bidirectional"))
      (node (ref "U4") (pin "20") (pinfunction "SDA_20") (pintype "bidirectional"))
      (node (ref "U5") (pin "20") (pinfunction "SDA_20") (pintype "bidirectional"))
      (node (ref "U6") (pin "20") (pinfunction "SDA_20") (pintype "bidirectional"))
    )
    (net (code "90") (name "SDA2") (class "Default")
      (node (ref "R46") (pin "2") (pinfunction "2_2") (pintype "passive"))
      (node (ref "U$4") (pin "25") (pinfunction "PA16/I2C/I0/SERCOM1+3.0_25") (pintype "bidirectional"))
      (node (ref "U10") (pin "20") (pinfunction "SDA_20") (pintype "bidirectional"))
      (node (ref "U11") (pin "20") (pinfunction "SDA_20") (pintype "bidirectional"))
      (node (ref "U12") (pin "20") (pinfunction "SDA_20") (pintype "bidirectional"))
      (node (ref "U7") (pin "20") (pinfunction "SDA_20") (pintype "bidirectional"))
      (node (ref "U8") (pin "20") (pinfunction "SDA_20") (pintype "bidirectional"))
      (node (ref "U9") (pin "20") (pinfunction "SDA_20") (pintype "bidirectional"))
    )
    (net (code "91") (name "SWCLK") (class "Default")
      (node (ref "PAD3") (pin "1") (pinfunction "P_1") (pintype "passive"))
      (node (ref "U$4") (pin "45") (pinfunction "PA30/I10/SECOM1.2/SWCLK_45") (pintype "bidirectional"))
    )
    (net (code "92") (name "SWDIO") (class "Default")
      (node (ref "PAD4") (pin "1") (pinfunction "P_1") (pintype "passive"))
      (node (ref "U$4") (pin "46") (pinfunction "PA31/I11/SECOM1.3/SWDIO_46") (pintype "bidirectional"))
    )
    (net (code "93") (name "TX") (class "Default")
      (node (ref "P2") (pin "2") (pinfunction "2_2") (pintype "passive"))
      (node (ref "U$4") (pin "15") (pinfunction "PA10/I10/AIN18/SERCOM0+2.2/I2SCK_15") (pintype "bidirectional"))
    )
    (net (code "94") (name "VBAT") (class "Default")
      (node (ref "D1") (pin "A") (pinfunction "A_A") (pintype "passive"))
      (node (ref "P2") (pin "5") (pinfunction "5_5") (pintype "passive"))
    )
    (net (code "95") (name "VBUS") (class "Default")
      (node (ref "C22") (pin "1") (pinfunction "1_1") (pintype "passive"))
      (node (ref "D1") (pin "C") (pinfunction "C_C") (pintype "passive"))
      (node (ref "R45") (pin "1") (pinfunction "1_1") (pintype "passive"))
      (node (ref "U13") (pin "1") (pinfunction "IN_1") (pintype "power_in"))
      (node (ref "X3") (pin "VBUS") (pinfunction "VBUS_VBUS") (pintype "power_in"))
    )
    (net (code "96") (name "unconnected-(U$4-PA13{slash}I13{slash}I2C{slash}SERCOM2+4.1-Pad22)") (class "Default")
      (node (ref "U$4") (pin "22") (pinfunction "PA13/I13/I2C/SERCOM2+4.1_22") (pintype "bidirectional"))
    )
    (net (code "97") (name "unconnected-(U$4-PA27{slash}I15-Pad39)") (class "Default")
      (node (ref "U$4") (pin "39") (pinfunction "PA27/I15_39") (pintype "bidirectional"))
    )
    (net (code "98") (name "unconnected-(U$4-PA28{slash}I8-Pad41)") (class "Default")
      (node (ref "U$4") (pin "41") (pinfunction "PA28/I8_41") (pintype "bidirectional"))
    )
    (net (code "99") (name "unconnected-(U$4-PB03{slash}I3{slash}AIN11{slash}SERCOM5.1-Pad48)") (class "Default")
      (node (ref "U$4") (pin "48") (pinfunction "PB03/I3/AIN11/SERCOM5.1_48") (pintype "bidirectional"))
    )
    (net (code "100") (name "unconnected-(U$4-PB22{slash}I6{slash}SERCOM5.2-Pad37)") (class "Default")
      (node (ref "U$4") (pin "37") (pinfunction "PB22/I6/SERCOM5.2_37") (pintype "bidirectional"))
    )
    (net (code "101") (name "unconnected-(U$4-PB23{slash}I7{slash}SERCOM5.3-Pad38)") (class "Default")
      (node (ref "U$4") (pin "38") (pinfunction "PB23/I7/SERCOM5.3_38") (pintype "bidirectional"))
    )
    (net (code "102") (name "unconnected-(U1-ALERT_1-Pad11)") (class "Default")
      (node (ref "U1") (pin "11") (pinfunction "ALERT_1_11") (pintype "output"))
    )
    (net (code "103") (name "unconnected-(U1-ALERT_2-Pad12)") (class "Default")
      (node (ref "U1") (pin "12") (pinfunction "ALERT_2_12") (pintype "output"))
    )
    (net (code "104") (name "unconnected-(U1-ALERT_3-Pad14)") (class "Default")
      (node (ref "U1") (pin "14") (pinfunction "ALERT_3_14") (pintype "output"))
    )
    (net (code "105") (name "unconnected-(U1-ALERT_4-Pad15)") (class "Default")
      (node (ref "U1") (pin "15") (pinfunction "ALERT_4_15") (pintype "output"))
    )
    (net (code "106") (name "unconnected-(U2-ALERT_1-Pad11)") (class "Default")
      (node (ref "U2") (pin "11") (pinfunction "ALERT_1_11") (pintype "output"))
    )
    (net (code "107") (name "unconnected-(U2-ALERT_2-Pad12)") (class "Default")
      (node (ref "U2") (pin "12") (pinfunction "ALERT_2_12") (pintype "output"))
    )
    (net (code "108") (name "unconnected-(U2-ALERT_3-Pad14)") (class "Default")
      (node (ref "U2") (pin "14") (pinfunction "ALERT_3_14") (pintype "output"))
    )
    (net (code "109") (name "unconnected-(U2-ALERT_4-Pad15)") (class "Default")
      (node (ref "U2") (pin "15") (pinfunction "ALERT_4_15") (pintype "output"))
    )
    (net (code "110") (name "unconnected-(U3-ALERT_1-Pad11)") (class "Default")
      (node (ref "U3") (pin "11") (pinfunction "ALERT_1_11") (pintype "output"))
    )
    (net (code "111") (name "unconnected-(U3-ALERT_2-Pad12)") (class "Default")
      (node (ref "U3") (pin "12") (pinfunction "ALERT_2_12") (pintype "output"))
    )
    (net (code "112") (name "unconnected-(U3-ALERT_3-Pad14)") (class "Default")
      (node (ref "U3") (pin "14") (pinfunction "ALERT_3_14") (pintype "output"))
    )
    (net (code "113") (name "unconnected-(U3-ALERT_4-Pad15)") (class "Default")
      (node (ref "U3") (pin "15") (pinfunction "ALERT_4_15") (pintype "output"))
    )
    (net (code "114") (name "unconnected-(U4-ALERT_1-Pad11)") (class "Default")
      (node (ref "U4") (pin "11") (pinfunction "ALERT_1_11") (pintype "output"))
    )
    (net (code "115") (name "unconnected-(U4-ALERT_2-Pad12)") (class "Default")
      (node (ref "U4") (pin "12") (pinfunction "ALERT_2_12") (pintype "output"))
    )
    (net (code "116") (name "unconnected-(U4-ALERT_3-Pad14)") (class "Default")
      (node (ref "U4") (pin "14") (pinfunction "ALERT_3_14") (pintype "output"))
    )
    (net (code "117") (name "unconnected-(U4-ALERT_4-Pad15)") (class "Default")
      (node (ref "U4") (pin "15") (pinfunction "ALERT_4_15") (pintype "output"))
    )
    (net (code "118") (name "unconnected-(U5-ALERT_1-Pad11)") (class "Default")
      (node (ref "U5") (pin "11") (pinfunction "ALERT_1_11") (pintype "output"))
    )
    (net (code "119") (name "unconnected-(U5-ALERT_2-Pad12)") (class "Default")
      (node (ref "U5") (pin "12") (pinfunction "ALERT_2_12") (pintype "output"))
    )
    (net (code "120") (name "unconnected-(U5-ALERT_3-Pad14)") (class "Default")
      (node (ref "U5") (pin "14") (pinfunction "ALERT_3_14") (pintype "output"))
    )
    (net (code "121") (name "unconnected-(U5-ALERT_4-Pad15)") (class "Default")
      (node (ref "U5") (pin "15") (pinfunction "ALERT_4_15") (pintype "output"))
    )
    (net (code "122") (name "unconnected-(U6-ALERT_1-Pad11)") (class "Default")
      (node (ref "U6") (pin "11") (pinfunction "ALERT_1_11") (pintype "output"))
    )
    (net (code "123") (name "unconnected-(U6-ALERT_2-Pad12)") (class "Default")
      (node (ref "U6") (pin "12") (pinfunction "ALERT_2_12") (pintype "output"))
    )
    (net (code "124") (name "unconnected-(U6-ALERT_3-Pad14)") (class "Default")
      (node (ref "U6") (pin "14") (pinfunction "ALERT_3_14") (pintype "output"))
    )
    (net (code "125") (name "unconnected-(U6-ALERT_4-Pad15)") (class "Default")
      (node (ref "U6") (pin "15") (pinfunction "ALERT_4_15") (pintype "output"))
    )
    (net (code "126") (name "unconnected-(U7-ALERT_1-Pad11)") (class "Default")
      (node (ref "U7") (pin "11") (pinfunction "ALERT_1_11") (pintype "output"))
    )
    (net (code "127") (name "unconnected-(U7-ALERT_2-Pad12)") (class "Default")
      (node (ref "U7") (pin "12") (pinfunction "ALERT_2_12") (pintype "output"))
    )
    (net (code "128") (name "unconnected-(U7-ALERT_3-Pad14)") (class "Default")
      (node (ref "U7") (pin "14") (pinfunction "ALERT_3_14") (pintype "output"))
    )
    (net (code "129") (name "unconnected-(U7-ALERT_4-Pad15)") (class "Default")
      (node (ref "U7") (pin "15") (pinfunction "ALERT_4_15") (pintype "output"))
    )
    (net (code "130") (name "unconnected-(U8-ALERT_1-Pad11)") (class "Default")
      (node (ref "U8") (pin "11") (pinfunction "ALERT_1_11") (pintype "output"))
    )
    (net (code "131") (name "unconnected-(U8-ALERT_2-Pad12)") (class "Default")
      (node (ref "U8") (pin "12") (pinfunction "ALERT_2_12") (pintype "output"))
    )
    (net (code "132") (name "unconnected-(U8-ALERT_3-Pad14)") (class "Default")
      (node (ref "U8") (pin "14") (pinfunction "ALERT_3_14") (pintype "output"))
    )
    (net (code "133") (name "unconnected-(U8-ALERT_4-Pad15)") (class "Default")
      (node (ref "U8") (pin "15") (pinfunction "ALERT_4_15") (pintype "output"))
    )
    (net (code "134") (name "unconnected-(U9-ALERT_1-Pad11)") (class "Default")
      (node (ref "U9") (pin "11") (pinfunction "ALERT_1_11") (pintype "output"))
    )
    (net (code "135") (name "unconnected-(U9-ALERT_2-Pad12)") (class "Default")
      (node (ref "U9") (pin "12") (pinfunction "ALERT_2_12") (pintype "output"))
    )
    (net (code "136") (name "unconnected-(U9-ALERT_3-Pad14)") (class "Default")
      (node (ref "U9") (pin "14") (pinfunction "ALERT_3_14") (pintype "output"))
    )
    (net (code "137") (name "unconnected-(U9-ALERT_4-Pad15)") (class "Default")
      (node (ref "U9") (pin "15") (pinfunction "ALERT_4_15") (pintype "output"))
    )
    (net (code "138") (name "unconnected-(U10-ALERT_1-Pad11)") (class "Default")
      (node (ref "U10") (pin "11") (pinfunction "ALERT_1_11") (pintype "output"))
    )
    (net (code "139") (name "unconnected-(U10-ALERT_2-Pad12)") (class "Default")
      (node (ref "U10") (pin "12") (pinfunction "ALERT_2_12") (pintype "output"))
    )
    (net (code "140") (name "unconnected-(U10-ALERT_3-Pad14)") (class "Default")
      (node (ref "U10") (pin "14") (pinfunction "ALERT_3_14") (pintype "output"))
    )
    (net (code "141") (name "unconnected-(U10-ALERT_4-Pad15)") (class "Default")
      (node (ref "U10") (pin "15") (pinfunction "ALERT_4_15") (pintype "output"))
    )
    (net (code "142") (name "unconnected-(U11-ALERT_1-Pad11)") (class "Default")
      (node (ref "U11") (pin "11") (pinfunction "ALERT_1_11") (pintype "output"))
    )
    (net (code "143") (name "unconnected-(U11-ALERT_2-Pad12)") (class "Default")
      (node (ref "U11") (pin "12") (pinfunction "ALERT_2_12") (pintype "output"))
    )
    (net (code "144") (name "unconnected-(U11-ALERT_3-Pad14)") (class "Default")
      (node (ref "U11") (pin "14") (pinfunction "ALERT_3_14") (pintype "output"))
    )
    (net (code "145") (name "unconnected-(U11-ALERT_4-Pad15)") (class "Default")
      (node (ref "U11") (pin "15") (pinfunction "ALERT_4_15") (pintype "output"))
    )
    (net (code "146") (name "unconnected-(U12-ALERT_1-Pad11)") (class "Default")
      (node (ref "U12") (pin "11") (pinfunction "ALERT_1_11") (pintype "output"))
    )
    (net (code "147") (name "unconnected-(U12-ALERT_2-Pad12)") (class "Default")
      (node (ref "U12") (pin "12") (pinfunction "ALERT_2_12") (pintype "output"))
    )
    (net (code "148") (name "unconnected-(U12-ALERT_3-Pad14)") (class "Default")
      (node (ref "U12") (pin "14") (pinfunction "ALERT_3_14") (pintype "output"))
    )
    (net (code "149") (name "unconnected-(U12-ALERT_4-Pad15)") (class "Default")
      (node (ref "U12") (pin "15") (pinfunction "ALERT_4_15") (pintype "output"))
    )
    (net (code "150") (name "unconnected-(U13-P4-Pad4)") (class "Default")
      (node (ref "U13") (pin "4") (pinfunction "P4_4") (pintype "bidirectional"))
    )
    (net (code "151") (name "unconnected-(X3-PadID)") (class "Default")
      (node (ref "X3") (pin "ID") (pinfunction "ID_ID") (pintype "bidirectional"))
    )
    (net (code "152") (name "~{RESET}") (class "Default")
      (node (ref "PAD2") (pin "1") (pinfunction "P_1") (pintype "passive"))
      (node (ref "U$4") (pin "40") (pinfunction "/RESET_40") (pintype "bidirectional"))
    )
  )
)
